# EHR.net
KiCad netlist of a schematic drawn in Altium Designer
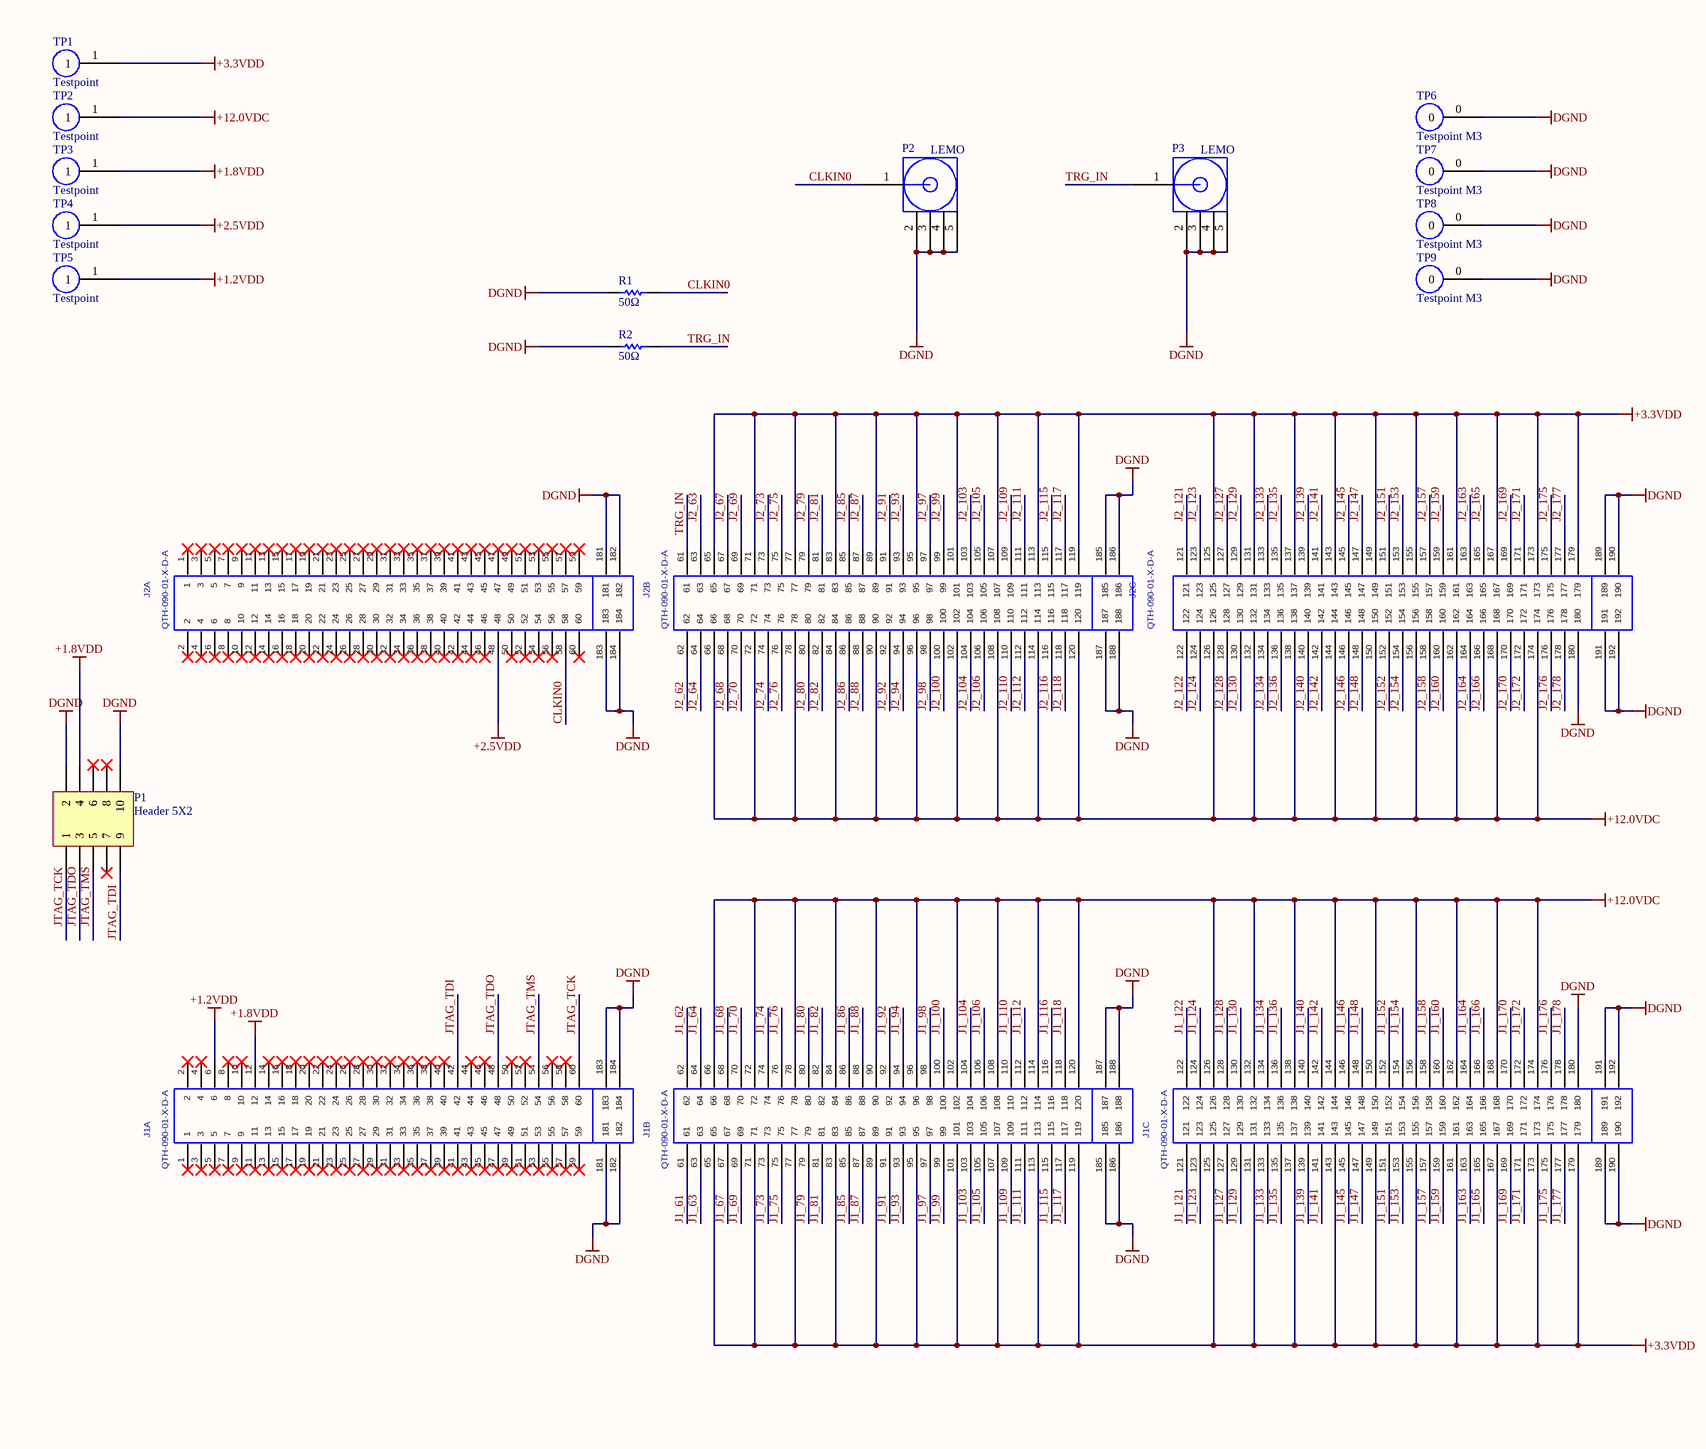
[diagram p0: EHR.SchDoc, left]
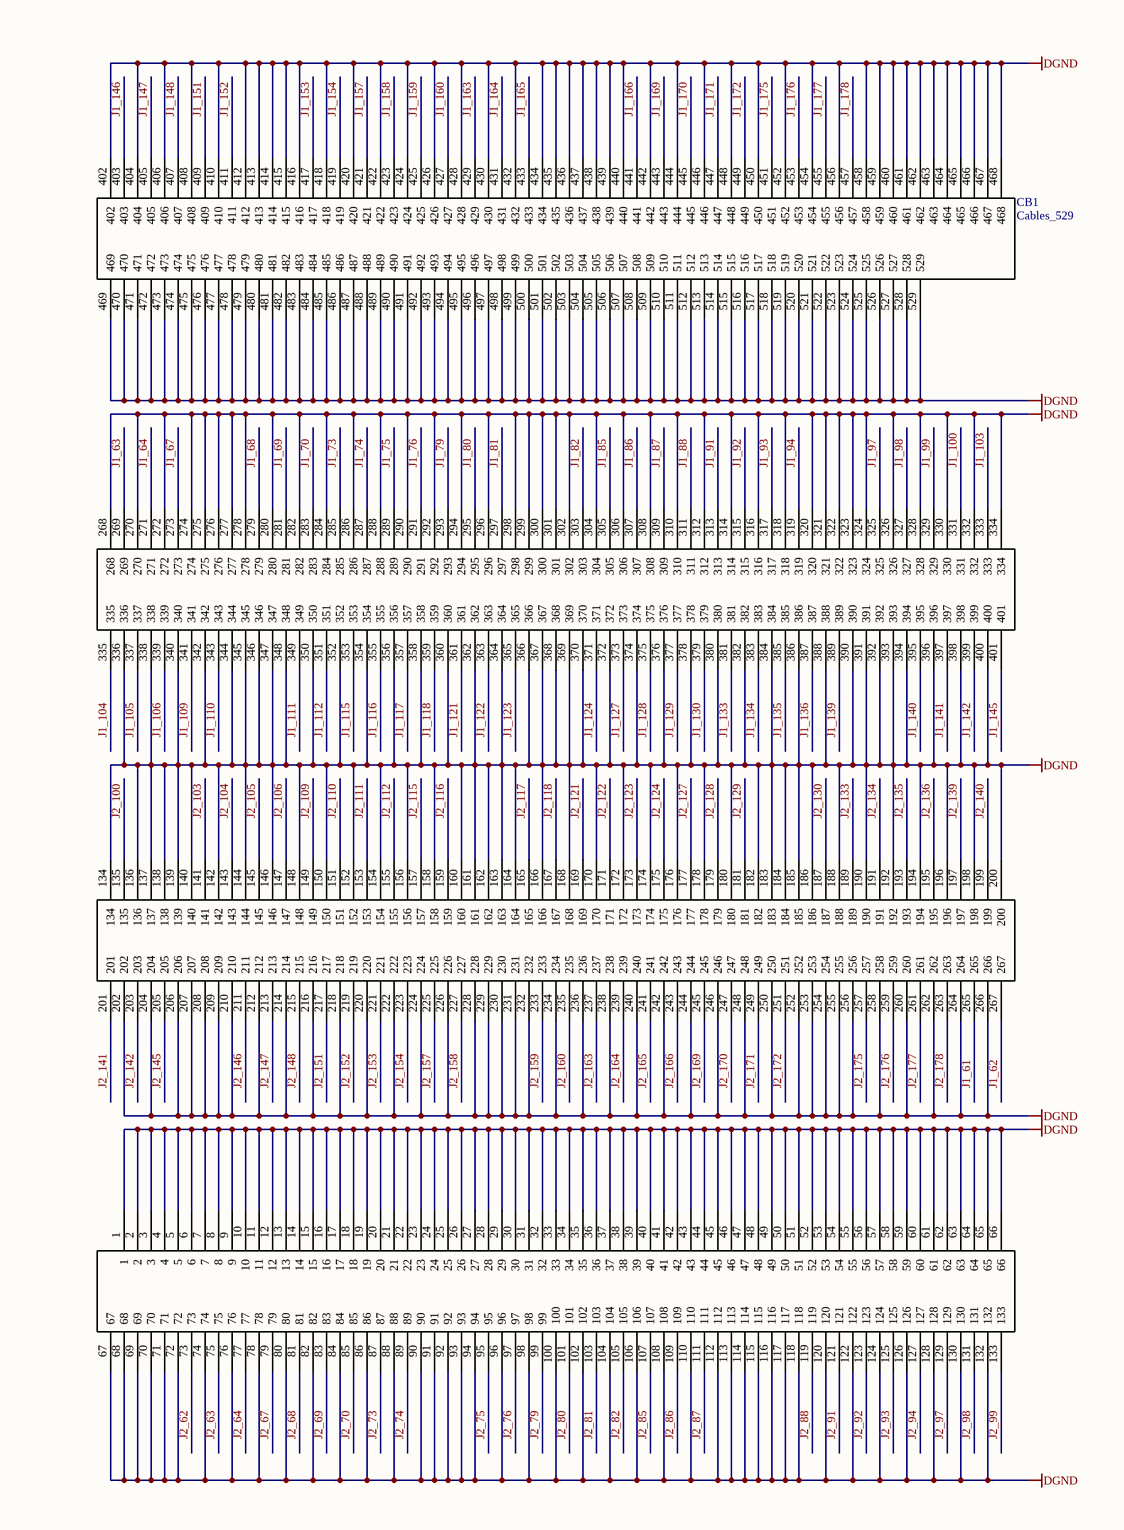
[diagram p1: EHR.SchDoc, right]

(export (version "E")
  (design (tool "Eeschema 10.0.6"))
  (components
    (comp (ref "CB1")
      (value "Cables_529")
      (footprint "EHR23x23_M3")
      (libsource (lib "User_parts") (part "Cables_529"))
    )
    (comp (ref "J1")
      (value "QTH-090-01-X-D-A")
      (footprint "QTH-090-01-X-D-A")
      (description "HIGH SPEED TERMINAL STRIP, .5mm PITCH, 180 PINS.")
      (fields (field (name "MANUFACTURER") "SAMTEC") (field (name "CREATED") "July 30, 2014 - WENDY XIN"))
      (libsource (lib "QTH-090-01-X-D-A") (part "QTH-090-01-X-D-A"))
    )
    (comp (ref "J2")
      (value "QTH-090-01-X-D-A")
      (footprint "QTH-090-01-X-D-A")
      (description "HIGH SPEED TERMINAL STRIP, .5mm PITCH, 180 PINS.")
      (fields (field (name "MANUFACTURER") "SAMTEC") (field (name "CREATED") "July 30, 2014 - WENDY XIN"))
      (libsource (lib "QTH-090-01-X-D-A") (part "QTH-090-01-X-D-A"))
    )
    (comp (ref "P1")
      (value "Header 5X2")
      (footprint "HDR2X5")
      (description "Header, 5-Pin, Dual row")
      (fields (field (name "PUBLISHER") "Altium Limited"))
      (libsource (lib "Miscellaneous Connectors") (part "Header 5X2"))
    )
    (comp (ref "P2") (value "LEMO") (footprint "LEMO_F") (libsource (lib "User_parts") (part "LEMO")))
    (comp (ref "P3") (value "LEMO") (footprint "LEMO_F") (libsource (lib "User_parts") (part "LEMO")))
    (comp (ref "R1")
      (value "50Ω")
      (footprint "AXIAL-0.3")
      (description "Resistor")
      (fields (field (name "PUBLISHER") "Altium Limited"))
      (libsource (lib "Miscellaneous Devices") (part "Res1"))
    )
    (comp (ref "R2")
      (value "50Ω")
      (footprint "AXIAL-0.3")
      (description "Resistor")
      (fields (field (name "PUBLISHER") "Altium Limited"))
      (libsource (lib "Miscellaneous Devices") (part "Res1"))
    )
    (comp (ref "TP1")
      (value "Testpoint")
      (footprint "Pad_mid")
      (description "Testpoint middle")
      (libsource (lib "User_parts") (part "Pad_med"))
    )
    (comp (ref "TP2")
      (value "Testpoint")
      (footprint "Pad_mid")
      (description "Testpoint middle")
      (libsource (lib "User_parts") (part "Pad_med"))
    )
    (comp (ref "TP3")
      (value "Testpoint")
      (footprint "Pad_mid")
      (description "Testpoint middle")
      (libsource (lib "User_parts") (part "Pad_med"))
    )
    (comp (ref "TP4")
      (value "Testpoint")
      (footprint "Pad_mid")
      (description "Testpoint middle")
      (libsource (lib "User_parts") (part "Pad_med"))
    )
    (comp (ref "TP5")
      (value "Testpoint")
      (footprint "Pad_mid")
      (description "Testpoint middle")
      (libsource (lib "User_parts") (part "Pad_med"))
    )
    (comp (ref "TP6")
      (value "Testpoint M3")
      (footprint "Testpoint_M3")
      (libsource (lib "User_parts") (part "Pad_M3"))
    )
    (comp (ref "TP7")
      (value "Testpoint M3")
      (footprint "Testpoint_M3")
      (libsource (lib "User_parts") (part "Pad_M3"))
    )
    (comp (ref "TP8")
      (value "Testpoint M3")
      (footprint "Testpoint_M3")
      (libsource (lib "User_parts") (part "Pad_M3"))
    )
    (comp (ref "TP9")
      (value "Testpoint M3")
      (footprint "Testpoint_M3")
      (libsource (lib "User_parts") (part "Pad_M3"))
    )
  )
  (nets
    (net (code "1") (name "+1.2VDD") (class "Default")
      (node (ref "J1") (pin "6") (pinfunction "6_6") (pintype "passive"))
      (node (ref "TP5") (pin "1") (pinfunction "1_1") (pintype "passive"))
    )
    (net (code "2") (name "+1.8VDD") (class "Default")
      (node (ref "J1") (pin "12") (pinfunction "12_12") (pintype "passive"))
      (node (ref "P1") (pin "4") (pinfunction "4_4") (pintype "passive"))
      (node (ref "TP3") (pin "1") (pinfunction "1_1") (pintype "passive"))
    )
    (net (code "3") (name "+2.5VDD") (class "Default")
      (node (ref "J2") (pin "48") (pinfunction "48_48") (pintype "passive"))
      (node (ref "TP4") (pin "1") (pinfunction "1_1") (pintype "passive"))
    )
    (net (code "4") (name "+3.3VDD") (class "Default")
      (node (ref "J1") (pin "101") (pinfunction "101_101") (pintype "passive"))
      (node (ref "J1") (pin "107") (pinfunction "107_107") (pintype "passive"))
      (node (ref "J1") (pin "113") (pinfunction "113_113") (pintype "passive"))
      (node (ref "J1") (pin "119") (pinfunction "119_119") (pintype "passive"))
      (node (ref "J1") (pin "125") (pinfunction "125_125") (pintype "passive"))
      (node (ref "J1") (pin "131") (pinfunction "131_131") (pintype "passive"))
      (node (ref "J1") (pin "137") (pinfunction "137_137") (pintype "passive"))
      (node (ref "J1") (pin "143") (pinfunction "143_143") (pintype "passive"))
      (node (ref "J1") (pin "149") (pinfunction "149_149") (pintype "passive"))
      (node (ref "J1") (pin "155") (pinfunction "155_155") (pintype "passive"))
      (node (ref "J1") (pin "161") (pinfunction "161_161") (pintype "passive"))
      (node (ref "J1") (pin "167") (pinfunction "167_167") (pintype "passive"))
      (node (ref "J1") (pin "173") (pinfunction "173_173") (pintype "passive"))
      (node (ref "J1") (pin "179") (pinfunction "179_179") (pintype "passive"))
      (node (ref "J1") (pin "65") (pinfunction "65_65") (pintype "passive"))
      (node (ref "J1") (pin "71") (pinfunction "71_71") (pintype "passive"))
      (node (ref "J1") (pin "77") (pinfunction "77_77") (pintype "passive"))
      (node (ref "J1") (pin "83") (pinfunction "83_83") (pintype "passive"))
      (node (ref "J1") (pin "89") (pinfunction "89_89") (pintype "passive"))
      (node (ref "J1") (pin "95") (pinfunction "95_95") (pintype "passive"))
      (node (ref "J2") (pin "101") (pinfunction "101_101") (pintype "passive"))
      (node (ref "J2") (pin "107") (pinfunction "107_107") (pintype "passive"))
      (node (ref "J2") (pin "113") (pinfunction "113_113") (pintype "passive"))
      (node (ref "J2") (pin "119") (pinfunction "119_119") (pintype "passive"))
      (node (ref "J2") (pin "125") (pinfunction "125_125") (pintype "passive"))
      (node (ref "J2") (pin "131") (pinfunction "131_131") (pintype "passive"))
      (node (ref "J2") (pin "137") (pinfunction "137_137") (pintype "passive"))
      (node (ref "J2") (pin "143") (pinfunction "143_143") (pintype "passive"))
      (node (ref "J2") (pin "149") (pinfunction "149_149") (pintype "passive"))
      (node (ref "J2") (pin "155") (pinfunction "155_155") (pintype "passive"))
      (node (ref "J2") (pin "161") (pinfunction "161_161") (pintype "passive"))
      (node (ref "J2") (pin "167") (pinfunction "167_167") (pintype "passive"))
      (node (ref "J2") (pin "173") (pinfunction "173_173") (pintype "passive"))
      (node (ref "J2") (pin "179") (pinfunction "179_179") (pintype "passive"))
      (node (ref "J2") (pin "65") (pinfunction "65_65") (pintype "passive"))
      (node (ref "J2") (pin "71") (pinfunction "71_71") (pintype "passive"))
      (node (ref "J2") (pin "77") (pinfunction "77_77") (pintype "passive"))
      (node (ref "J2") (pin "83") (pinfunction "83_83") (pintype "passive"))
      (node (ref "J2") (pin "89") (pinfunction "89_89") (pintype "passive"))
      (node (ref "J2") (pin "95") (pinfunction "95_95") (pintype "passive"))
      (node (ref "TP1") (pin "1") (pinfunction "1_1") (pintype "passive"))
    )
    (net (code "5") (name "+12.0VDC") (class "Default")
      (node (ref "J1") (pin "102") (pinfunction "102_102") (pintype "passive"))
      (node (ref "J1") (pin "108") (pinfunction "108_108") (pintype "passive"))
      (node (ref "J1") (pin "114") (pinfunction "114_114") (pintype "passive"))
      (node (ref "J1") (pin "120") (pinfunction "120_120") (pintype "passive"))
      (node (ref "J1") (pin "126") (pinfunction "126_126") (pintype "passive"))
      (node (ref "J1") (pin "132") (pinfunction "132_132") (pintype "passive"))
      (node (ref "J1") (pin "138") (pinfunction "138_138") (pintype "passive"))
      (node (ref "J1") (pin "144") (pinfunction "144_144") (pintype "passive"))
      (node (ref "J1") (pin "150") (pinfunction "150_150") (pintype "passive"))
      (node (ref "J1") (pin "156") (pinfunction "156_156") (pintype "passive"))
      (node (ref "J1") (pin "162") (pinfunction "162_162") (pintype "passive"))
      (node (ref "J1") (pin "168") (pinfunction "168_168") (pintype "passive"))
      (node (ref "J1") (pin "174") (pinfunction "174_174") (pintype "passive"))
      (node (ref "J1") (pin "66") (pinfunction "66_66") (pintype "passive"))
      (node (ref "J1") (pin "72") (pinfunction "72_72") (pintype "passive"))
      (node (ref "J1") (pin "78") (pinfunction "78_78") (pintype "passive"))
      (node (ref "J1") (pin "84") (pinfunction "84_84") (pintype "passive"))
      (node (ref "J1") (pin "90") (pinfunction "90_90") (pintype "passive"))
      (node (ref "J1") (pin "96") (pinfunction "96_96") (pintype "passive"))
      (node (ref "J2") (pin "102") (pinfunction "102_102") (pintype "passive"))
      (node (ref "J2") (pin "108") (pinfunction "108_108") (pintype "passive"))
      (node (ref "J2") (pin "114") (pinfunction "114_114") (pintype "passive"))
      (node (ref "J2") (pin "120") (pinfunction "120_120") (pintype "passive"))
      (node (ref "J2") (pin "126") (pinfunction "126_126") (pintype "passive"))
      (node (ref "J2") (pin "132") (pinfunction "132_132") (pintype "passive"))
      (node (ref "J2") (pin "138") (pinfunction "138_138") (pintype "passive"))
      (node (ref "J2") (pin "144") (pinfunction "144_144") (pintype "passive"))
      (node (ref "J2") (pin "150") (pinfunction "150_150") (pintype "passive"))
      (node (ref "J2") (pin "156") (pinfunction "156_156") (pintype "passive"))
      (node (ref "J2") (pin "162") (pinfunction "162_162") (pintype "passive"))
      (node (ref "J2") (pin "168") (pinfunction "168_168") (pintype "passive"))
      (node (ref "J2") (pin "174") (pinfunction "174_174") (pintype "passive"))
      (node (ref "J2") (pin "66") (pinfunction "66_66") (pintype "passive"))
      (node (ref "J2") (pin "72") (pinfunction "72_72") (pintype "passive"))
      (node (ref "J2") (pin "78") (pinfunction "78_78") (pintype "passive"))
      (node (ref "J2") (pin "84") (pinfunction "84_84") (pintype "passive"))
      (node (ref "J2") (pin "90") (pinfunction "90_90") (pintype "passive"))
      (node (ref "J2") (pin "96") (pinfunction "96_96") (pintype "passive"))
      (node (ref "TP2") (pin "1") (pinfunction "1_1") (pintype "passive"))
    )
    (net (code "6") (name "/CLKIN0") (class "Default")
      (node (ref "J2") (pin "58") (pinfunction "58_58") (pintype "passive"))
      (node (ref "P2") (pin "1") (pinfunction "0_1") (pintype "passive"))
      (node (ref "R1") (pin "2") (pinfunction "2_2") (pintype "passive"))
    )
    (net (code "7") (name "/J1_61") (class "Default")
      (node (ref "CB1") (pin "265") (pinfunction "265_265") (pintype "passive"))
      (node (ref "J1") (pin "61") (pinfunction "61_61") (pintype "passive"))
    )
    (net (code "8") (name "/J1_62") (class "Default")
      (node (ref "CB1") (pin "267") (pinfunction "267_267") (pintype "passive"))
      (node (ref "J1") (pin "62") (pinfunction "62_62") (pintype "passive"))
    )
    (net (code "9") (name "/J1_63") (class "Default")
      (node (ref "CB1") (pin "269") (pinfunction "269_269") (pintype "passive"))
      (node (ref "J1") (pin "63") (pinfunction "63_63") (pintype "passive"))
    )
    (net (code "10") (name "/J1_64") (class "Default")
      (node (ref "CB1") (pin "271") (pinfunction "271_271") (pintype "passive"))
      (node (ref "J1") (pin "64") (pinfunction "64_64") (pintype "passive"))
    )
    (net (code "11") (name "/J1_67") (class "Default")
      (node (ref "CB1") (pin "273") (pinfunction "273_273") (pintype "passive"))
      (node (ref "J1") (pin "67") (pinfunction "67_67") (pintype "passive"))
    )
    (net (code "12") (name "/J1_68") (class "Default")
      (node (ref "CB1") (pin "279") (pinfunction "279_279") (pintype "passive"))
      (node (ref "J1") (pin "68") (pinfunction "68_68") (pintype "passive"))
    )
    (net (code "13") (name "/J1_69") (class "Default")
      (node (ref "CB1") (pin "281") (pinfunction "281_281") (pintype "passive"))
      (node (ref "J1") (pin "69") (pinfunction "69_69") (pintype "passive"))
    )
    (net (code "14") (name "/J1_70") (class "Default")
      (node (ref "CB1") (pin "283") (pinfunction "283_283") (pintype "passive"))
      (node (ref "J1") (pin "70") (pinfunction "70_70") (pintype "passive"))
    )
    (net (code "15") (name "/J1_73") (class "Default")
      (node (ref "CB1") (pin "285") (pinfunction "285_285") (pintype "passive"))
      (node (ref "J1") (pin "73") (pinfunction "73_73") (pintype "passive"))
    )
    (net (code "16") (name "/J1_74") (class "Default")
      (node (ref "CB1") (pin "287") (pinfunction "287_287") (pintype "passive"))
      (node (ref "J1") (pin "74") (pinfunction "74_74") (pintype "passive"))
    )
    (net (code "17") (name "/J1_75") (class "Default")
      (node (ref "CB1") (pin "289") (pinfunction "289_289") (pintype "passive"))
      (node (ref "J1") (pin "75") (pinfunction "75_75") (pintype "passive"))
    )
    (net (code "18") (name "/J1_76") (class "Default")
      (node (ref "CB1") (pin "291") (pinfunction "291_291") (pintype "passive"))
      (node (ref "J1") (pin "76") (pinfunction "76_76") (pintype "passive"))
    )
    (net (code "19") (name "/J1_79") (class "Default")
      (node (ref "CB1") (pin "293") (pinfunction "293_293") (pintype "passive"))
      (node (ref "J1") (pin "79") (pinfunction "79_79") (pintype "passive"))
    )
    (net (code "20") (name "/J1_80") (class "Default")
      (node (ref "CB1") (pin "295") (pinfunction "295_295") (pintype "passive"))
      (node (ref "J1") (pin "80") (pinfunction "80_80") (pintype "passive"))
    )
    (net (code "21") (name "/J1_81") (class "Default")
      (node (ref "CB1") (pin "297") (pinfunction "297_297") (pintype "passive"))
      (node (ref "J1") (pin "81") (pinfunction "81_81") (pintype "passive"))
    )
    (net (code "22") (name "/J1_82") (class "Default")
      (node (ref "CB1") (pin "303") (pinfunction "303_303") (pintype "passive"))
      (node (ref "J1") (pin "82") (pinfunction "82_82") (pintype "passive"))
    )
    (net (code "23") (name "/J1_85") (class "Default")
      (node (ref "CB1") (pin "305") (pinfunction "305_305") (pintype "passive"))
      (node (ref "J1") (pin "85") (pinfunction "85_85") (pintype "passive"))
    )
    (net (code "24") (name "/J1_86") (class "Default")
      (node (ref "CB1") (pin "307") (pinfunction "307_307") (pintype "passive"))
      (node (ref "J1") (pin "86") (pinfunction "86_86") (pintype "passive"))
    )
    (net (code "25") (name "/J1_87") (class "Default")
      (node (ref "CB1") (pin "309") (pinfunction "309_309") (pintype "passive"))
      (node (ref "J1") (pin "87") (pinfunction "87_87") (pintype "passive"))
    )
    (net (code "26") (name "/J1_88") (class "Default")
      (node (ref "CB1") (pin "311") (pinfunction "311_311") (pintype "passive"))
      (node (ref "J1") (pin "88") (pinfunction "88_88") (pintype "passive"))
    )
    (net (code "27") (name "/J1_91") (class "Default")
      (node (ref "CB1") (pin "313") (pinfunction "313_313") (pintype "passive"))
      (node (ref "J1") (pin "91") (pinfunction "91_91") (pintype "passive"))
    )
    (net (code "28") (name "/J1_92") (class "Default")
      (node (ref "CB1") (pin "315") (pinfunction "315_315") (pintype "passive"))
      (node (ref "J1") (pin "92") (pinfunction "92_92") (pintype "passive"))
    )
    (net (code "29") (name "/J1_93") (class "Default")
      (node (ref "CB1") (pin "317") (pinfunction "317_317") (pintype "passive"))
      (node (ref "J1") (pin "93") (pinfunction "93_93") (pintype "passive"))
    )
    (net (code "30") (name "/J1_94") (class "Default")
      (node (ref "CB1") (pin "319") (pinfunction "319_319") (pintype "passive"))
      (node (ref "J1") (pin "94") (pinfunction "94_94") (pintype "passive"))
    )
    (net (code "31") (name "/J1_97") (class "Default")
      (node (ref "CB1") (pin "325") (pinfunction "325_325") (pintype "passive"))
      (node (ref "J1") (pin "97") (pinfunction "97_97") (pintype "passive"))
    )
    (net (code "32") (name "/J1_98") (class "Default")
      (node (ref "CB1") (pin "327") (pinfunction "327_327") (pintype "passive"))
      (node (ref "J1") (pin "98") (pinfunction "98_98") (pintype "passive"))
    )
    (net (code "33") (name "/J1_99") (class "Default")
      (node (ref "CB1") (pin "329") (pinfunction "329_329") (pintype "passive"))
      (node (ref "J1") (pin "99") (pinfunction "99_99") (pintype "passive"))
    )
    (net (code "34") (name "/J1_100") (class "Default")
      (node (ref "CB1") (pin "331") (pinfunction "331_331") (pintype "passive"))
      (node (ref "J1") (pin "100") (pinfunction "100_100") (pintype "passive"))
    )
    (net (code "35") (name "/J1_103") (class "Default")
      (node (ref "CB1") (pin "333") (pinfunction "333_333") (pintype "passive"))
      (node (ref "J1") (pin "103") (pinfunction "103_103") (pintype "passive"))
    )
    (net (code "36") (name "/J1_104") (class "Default")
      (node (ref "CB1") (pin "335") (pinfunction "335_335") (pintype "passive"))
      (node (ref "J1") (pin "104") (pinfunction "104_104") (pintype "passive"))
    )
    (net (code "37") (name "/J1_105") (class "Default")
      (node (ref "CB1") (pin "337") (pinfunction "337_337") (pintype "passive"))
      (node (ref "J1") (pin "105") (pinfunction "105_105") (pintype "passive"))
    )
    (net (code "38") (name "/J1_106") (class "Default")
      (node (ref "CB1") (pin "339") (pinfunction "339_339") (pintype "passive"))
      (node (ref "J1") (pin "106") (pinfunction "106_106") (pintype "passive"))
    )
    (net (code "39") (name "/J1_109") (class "Default")
      (node (ref "CB1") (pin "341") (pinfunction "341_341") (pintype "passive"))
      (node (ref "J1") (pin "109") (pinfunction "109_109") (pintype "passive"))
    )
    (net (code "40") (name "/J1_110") (class "Default")
      (node (ref "CB1") (pin "343") (pinfunction "343_343") (pintype "passive"))
      (node (ref "J1") (pin "110") (pinfunction "110_110") (pintype "passive"))
    )
    (net (code "41") (name "/J1_111") (class "Default")
      (node (ref "CB1") (pin "349") (pinfunction "349_349") (pintype "passive"))
      (node (ref "J1") (pin "111") (pinfunction "111_111") (pintype "passive"))
    )
    (net (code "42") (name "/J1_112") (class "Default")
      (node (ref "CB1") (pin "351") (pinfunction "351_351") (pintype "passive"))
      (node (ref "J1") (pin "112") (pinfunction "112_112") (pintype "passive"))
    )
    (net (code "43") (name "/J1_115") (class "Default")
      (node (ref "CB1") (pin "353") (pinfunction "353_353") (pintype "passive"))
      (node (ref "J1") (pin "115") (pinfunction "115_115") (pintype "passive"))
    )
    (net (code "44") (name "/J1_116") (class "Default")
      (node (ref "CB1") (pin "355") (pinfunction "355_355") (pintype "passive"))
      (node (ref "J1") (pin "116") (pinfunction "116_116") (pintype "passive"))
    )
    (net (code "45") (name "/J1_117") (class "Default")
      (node (ref "CB1") (pin "357") (pinfunction "357_357") (pintype "passive"))
      (node (ref "J1") (pin "117") (pinfunction "117_117") (pintype "passive"))
    )
    (net (code "46") (name "/J1_118") (class "Default")
      (node (ref "CB1") (pin "359") (pinfunction "359_359") (pintype "passive"))
      (node (ref "J1") (pin "118") (pinfunction "118_118") (pintype "passive"))
    )
    (net (code "47") (name "/J1_121") (class "Default")
      (node (ref "CB1") (pin "361") (pinfunction "361_361") (pintype "passive"))
      (node (ref "J1") (pin "121") (pinfunction "121_121") (pintype "passive"))
    )
    (net (code "48") (name "/J1_122") (class "Default")
      (node (ref "CB1") (pin "363") (pinfunction "363_363") (pintype "passive"))
      (node (ref "J1") (pin "122") (pinfunction "122_122") (pintype "passive"))
    )
    (net (code "49") (name "/J1_123") (class "Default")
      (node (ref "CB1") (pin "365") (pinfunction "365_365") (pintype "passive"))
      (node (ref "J1") (pin "123") (pinfunction "123_123") (pintype "passive"))
    )
    (net (code "50") (name "/J1_124") (class "Default")
      (node (ref "CB1") (pin "371") (pinfunction "371_371") (pintype "passive"))
      (node (ref "J1") (pin "124") (pinfunction "124_124") (pintype "passive"))
    )
    (net (code "51") (name "/J1_127") (class "Default")
      (node (ref "CB1") (pin "373") (pinfunction "373_373") (pintype "passive"))
      (node (ref "J1") (pin "127") (pinfunction "127_127") (pintype "passive"))
    )
    (net (code "52") (name "/J1_128") (class "Default")
      (node (ref "CB1") (pin "375") (pinfunction "375_375") (pintype "passive"))
      (node (ref "J1") (pin "128") (pinfunction "128_128") (pintype "passive"))
    )
    (net (code "53") (name "/J1_129") (class "Default")
      (node (ref "CB1") (pin "377") (pinfunction "377_377") (pintype "passive"))
      (node (ref "J1") (pin "129") (pinfunction "129_129") (pintype "passive"))
    )
    (net (code "54") (name "/J1_130") (class "Default")
      (node (ref "CB1") (pin "379") (pinfunction "379_379") (pintype "passive"))
      (node (ref "J1") (pin "130") (pinfunction "130_130") (pintype "passive"))
    )
    (net (code "55") (name "/J1_133") (class "Default")
      (node (ref "CB1") (pin "381") (pinfunction "381_381") (pintype "passive"))
      (node (ref "J1") (pin "133") (pinfunction "133_133") (pintype "passive"))
    )
    (net (code "56") (name "/J1_134") (class "Default")
      (node (ref "CB1") (pin "383") (pinfunction "383_383") (pintype "passive"))
      (node (ref "J1") (pin "134") (pinfunction "134_134") (pintype "passive"))
    )
    (net (code "57") (name "/J1_135") (class "Default")
      (node (ref "CB1") (pin "385") (pinfunction "385_385") (pintype "passive"))
      (node (ref "J1") (pin "135") (pinfunction "135_135") (pintype "passive"))
    )
    (net (code "58") (name "/J1_136") (class "Default")
      (node (ref "CB1") (pin "387") (pinfunction "387_387") (pintype "passive"))
      (node (ref "J1") (pin "136") (pinfunction "136_136") (pintype "passive"))
    )
    (net (code "59") (name "/J1_139") (class "Default")
      (node (ref "CB1") (pin "389") (pinfunction "389_389") (pintype "passive"))
      (node (ref "J1") (pin "139") (pinfunction "139_139") (pintype "passive"))
    )
    (net (code "60") (name "/J1_140") (class "Default")
      (node (ref "CB1") (pin "395") (pinfunction "395_395") (pintype "passive"))
      (node (ref "J1") (pin "140") (pinfunction "140_140") (pintype "passive"))
    )
    (net (code "61") (name "/J1_141") (class "Default")
      (node (ref "CB1") (pin "397") (pinfunction "397_397") (pintype "passive"))
      (node (ref "J1") (pin "141") (pinfunction "141_141") (pintype "passive"))
    )
    (net (code "62") (name "/J1_142") (class "Default")
      (node (ref "CB1") (pin "399") (pinfunction "399_399") (pintype "passive"))
      (node (ref "J1") (pin "142") (pinfunction "142_142") (pintype "passive"))
    )
    (net (code "63") (name "/J1_145") (class "Default")
      (node (ref "CB1") (pin "401") (pinfunction "401_401") (pintype "passive"))
      (node (ref "J1") (pin "145") (pinfunction "145_145") (pintype "passive"))
    )
    (net (code "64") (name "/J1_146") (class "Default")
      (node (ref "CB1") (pin "403") (pinfunction "403_403") (pintype "passive"))
      (node (ref "J1") (pin "146") (pinfunction "146_146") (pintype "passive"))
    )
    (net (code "65") (name "/J1_147") (class "Default")
      (node (ref "CB1") (pin "405") (pinfunction "405_405") (pintype "passive"))
      (node (ref "J1") (pin "147") (pinfunction "147_147") (pintype "passive"))
    )
    (net (code "66") (name "/J1_148") (class "Default")
      (node (ref "CB1") (pin "407") (pinfunction "407_407") (pintype "passive"))
      (node (ref "J1") (pin "148") (pinfunction "148_148") (pintype "passive"))
    )
    (net (code "67") (name "/J1_151") (class "Default")
      (node (ref "CB1") (pin "409") (pinfunction "409_409") (pintype "passive"))
      (node (ref "J1") (pin "151") (pinfunction "151_151") (pintype "passive"))
    )
    (net (code "68") (name "/J1_152") (class "Default")
      (node (ref "CB1") (pin "411") (pinfunction "411_411") (pintype "passive"))
      (node (ref "J1") (pin "152") (pinfunction "152_152") (pintype "passive"))
    )
    (net (code "69") (name "/J1_153") (class "Default")
      (node (ref "CB1") (pin "417") (pinfunction "417_417") (pintype "passive"))
      (node (ref "J1") (pin "153") (pinfunction "153_153") (pintype "passive"))
    )
    (net (code "70") (name "/J1_154") (class "Default")
      (node (ref "CB1") (pin "419") (pinfunction "419_419") (pintype "passive"))
      (node (ref "J1") (pin "154") (pinfunction "154_154") (pintype "passive"))
    )
    (net (code "71") (name "/J1_157") (class "Default")
      (node (ref "CB1") (pin "421") (pinfunction "421_421") (pintype "passive"))
      (node (ref "J1") (pin "157") (pinfunction "157_157") (pintype "passive"))
    )
    (net (code "72") (name "/J1_158") (class "Default")
      (node (ref "CB1") (pin "423") (pinfunction "423_423") (pintype "passive"))
      (node (ref "J1") (pin "158") (pinfunction "158_158") (pintype "passive"))
    )
    (net (code "73") (name "/J1_159") (class "Default")
      (node (ref "CB1") (pin "425") (pinfunction "425_425") (pintype "passive"))
      (node (ref "J1") (pin "159") (pinfunction "159_159") (pintype "passive"))
    )
    (net (code "74") (name "/J1_160") (class "Default")
      (node (ref "CB1") (pin "427") (pinfunction "427_427") (pintype "passive"))
      (node (ref "J1") (pin "160") (pinfunction "160_160") (pintype "passive"))
    )
    (net (code "75") (name "/J1_163") (class "Default")
      (node (ref "CB1") (pin "429") (pinfunction "429_429") (pintype "passive"))
      (node (ref "J1") (pin "163") (pinfunction "163_163") (pintype "passive"))
    )
    (net (code "76") (name "/J1_164") (class "Default")
      (node (ref "CB1") (pin "431") (pinfunction "431_431") (pintype "passive"))
      (node (ref "J1") (pin "164") (pinfunction "164_164") (pintype "passive"))
    )
    (net (code "77") (name "/J1_165") (class "Default")
      (node (ref "CB1") (pin "433") (pinfunction "433_433") (pintype "passive"))
      (node (ref "J1") (pin "165") (pinfunction "165_165") (pintype "passive"))
    )
    (net (code "78") (name "/J1_166") (class "Default")
      (node (ref "CB1") (pin "441") (pinfunction "441_441") (pintype "passive"))
      (node (ref "J1") (pin "166") (pinfunction "166_166") (pintype "passive"))
    )
    (net (code "79") (name "/J1_169") (class "Default")
      (node (ref "CB1") (pin "443") (pinfunction "443_443") (pintype "passive"))
      (node (ref "J1") (pin "169") (pinfunction "169_169") (pintype "passive"))
    )
    (net (code "80") (name "/J1_170") (class "Default")
      (node (ref "CB1") (pin "445") (pinfunction "445_445") (pintype "passive"))
      (node (ref "J1") (pin "170") (pinfunction "170_170") (pintype "passive"))
    )
    (net (code "81") (name "/J1_171") (class "Default")
      (node (ref "CB1") (pin "447") (pinfunction "447_447") (pintype "passive"))
      (node (ref "J1") (pin "171") (pinfunction "171_171") (pintype "passive"))
    )
    (net (code "82") (name "/J1_172") (class "Default")
      (node (ref "CB1") (pin "449") (pinfunction "449_449") (pintype "passive"))
      (node (ref "J1") (pin "172") (pinfunction "172_172") (pintype "passive"))
    )
    (net (code "83") (name "/J1_175") (class "Default")
      (node (ref "CB1") (pin "451") (pinfunction "451_451") (pintype "passive"))
      (node (ref "J1") (pin "175") (pinfunction "175_175") (pintype "passive"))
    )
    (net (code "84") (name "/J1_176") (class "Default")
      (node (ref "CB1") (pin "453") (pinfunction "453_453") (pintype "passive"))
      (node (ref "J1") (pin "176") (pinfunction "176_176") (pintype "passive"))
    )
    (net (code "85") (name "/J1_177") (class "Default")
      (node (ref "CB1") (pin "455") (pinfunction "455_455") (pintype "passive"))
      (node (ref "J1") (pin "177") (pinfunction "177_177") (pintype "passive"))
    )
    (net (code "86") (name "/J1_178") (class "Default")
      (node (ref "CB1") (pin "457") (pinfunction "457_457") (pintype "passive"))
      (node (ref "J1") (pin "178") (pinfunction "178_178") (pintype "passive"))
    )
    (net (code "87") (name "/J2_62") (class "Default")
      (node (ref "CB1") (pin "73") (pinfunction "73_73") (pintype "passive"))
      (node (ref "J2") (pin "62") (pinfunction "62_62") (pintype "passive"))
    )
    (net (code "88") (name "/J2_63") (class "Default")
      (node (ref "CB1") (pin "75") (pinfunction "75_75") (pintype "passive"))
      (node (ref "J2") (pin "63") (pinfunction "63_63") (pintype "passive"))
    )
    (net (code "89") (name "/J2_64") (class "Default")
      (node (ref "CB1") (pin "77") (pinfunction "77_77") (pintype "passive"))
      (node (ref "J2") (pin "64") (pinfunction "64_64") (pintype "passive"))
    )
    (net (code "90") (name "/J2_67") (class "Default")
      (node (ref "CB1") (pin "79") (pinfunction "79_79") (pintype "passive"))
      (node (ref "J2") (pin "67") (pinfunction "67_67") (pintype "passive"))
    )
    (net (code "91") (name "/J2_68") (class "Default")
      (node (ref "CB1") (pin "81") (pinfunction "81_81") (pintype "passive"))
      (node (ref "J2") (pin "68") (pinfunction "68_68") (pintype "passive"))
    )
    (net (code "92") (name "/J2_69") (class "Default")
      (node (ref "CB1") (pin "83") (pinfunction "83_83") (pintype "passive"))
      (node (ref "J2") (pin "69") (pinfunction "69_69") (pintype "passive"))
    )
    (net (code "93") (name "/J2_70") (class "Default")
      (node (ref "CB1") (pin "85") (pinfunction "85_85") (pintype "passive"))
      (node (ref "J2") (pin "70") (pinfunction "70_70") (pintype "passive"))
    )
    (net (code "94") (name "/J2_73") (class "Default")
      (node (ref "CB1") (pin "87") (pinfunction "87_87") (pintype "passive"))
      (node (ref "J2") (pin "73") (pinfunction "73_73") (pintype "passive"))
    )
    (net (code "95") (name "/J2_74") (class "Default")
      (node (ref "CB1") (pin "89") (pinfunction "89_89") (pintype "passive"))
      (node (ref "J2") (pin "74") (pinfunction "74_74") (pintype "passive"))
    )
    (net (code "96") (name "/J2_75") (class "Default")
      (node (ref "CB1") (pin "95") (pinfunction "95_95") (pintype "passive"))
      (node (ref "J2") (pin "75") (pinfunction "75_75") (pintype "passive"))
    )
    (net (code "97") (name "/J2_76") (class "Default")
      (node (ref "CB1") (pin "97") (pinfunction "97_97") (pintype "passive"))
      (node (ref "J2") (pin "76") (pinfunction "76_76") (pintype "passive"))
    )
    (net (code "98") (name "/J2_79") (class "Default")
      (node (ref "CB1") (pin "99") (pinfunction "99_99") (pintype "passive"))
      (node (ref "J2") (pin "79") (pinfunction "79_79") (pintype "passive"))
    )
    (net (code "99") (name "/J2_80") (class "Default")
      (node (ref "CB1") (pin "101") (pinfunction "101_101") (pintype "passive"))
      (node (ref "J2") (pin "80") (pinfunction "80_80") (pintype "passive"))
    )
    (net (code "100") (name "/J2_81") (class "Default")
      (node (ref "CB1") (pin "103") (pinfunction "103_103") (pintype "passive"))
      (node (ref "J2") (pin "81") (pinfunction "81_81") (pintype "passive"))
    )
    (net (code "101") (name "/J2_82") (class "Default")
      (node (ref "CB1") (pin "105") (pinfunction "105_105") (pintype "passive"))
      (node (ref "J2") (pin "82") (pinfunction "82_82") (pintype "passive"))
    )
    (net (code "102") (name "/J2_85") (class "Default")
      (node (ref "CB1") (pin "107") (pinfunction "107_107") (pintype "passive"))
      (node (ref "J2") (pin "85") (pinfunction "85_85") (pintype "passive"))
    )
    (net (code "103") (name "/J2_86") (class "Default")
      (node (ref "CB1") (pin "109") (pinfunction "109_109") (pintype "passive"))
      (node (ref "J2") (pin "86") (pinfunction "86_86") (pintype "passive"))
    )
    (net (code "104") (name "/J2_87") (class "Default")
      (node (ref "CB1") (pin "111") (pinfunction "111_111") (pintype "passive"))
      (node (ref "J2") (pin "87") (pinfunction "87_87") (pintype "passive"))
    )
    (net (code "105") (name "/J2_88") (class "Default")
      (node (ref "CB1") (pin "119") (pinfunction "119_119") (pintype "passive"))
      (node (ref "J2") (pin "88") (pinfunction "88_88") (pintype "passive"))
    )
    (net (code "106") (name "/J2_91") (class "Default")
      (node (ref "CB1") (pin "121") (pinfunction "121_121") (pintype "passive"))
      (node (ref "J2") (pin "91") (pinfunction "91_91") (pintype "passive"))
    )
    (net (code "107") (name "/J2_92") (class "Default")
      (node (ref "CB1") (pin "123") (pinfunction "123_123") (pintype "passive"))
      (node (ref "J2") (pin "92") (pinfunction "92_92") (pintype "passive"))
    )
    (net (code "108") (name "/J2_93") (class "Default")
      (node (ref "CB1") (pin "125") (pinfunction "125_125") (pintype "passive"))
      (node (ref "J2") (pin "93") (pinfunction "93_93") (pintype "passive"))
    )
    (net (code "109") (name "/J2_94") (class "Default")
      (node (ref "CB1") (pin "127") (pinfunction "127_127") (pintype "passive"))
      (node (ref "J2") (pin "94") (pinfunction "94_94") (pintype "passive"))
    )
    (net (code "110") (name "/J2_97") (class "Default")
      (node (ref "CB1") (pin "129") (pinfunction "129_129") (pintype "passive"))
      (node (ref "J2") (pin "97") (pinfunction "97_97") (pintype "passive"))
    )
    (net (code "111") (name "/J2_98") (class "Default")
      (node (ref "CB1") (pin "131") (pinfunction "131_131") (pintype "passive"))
      (node (ref "J2") (pin "98") (pinfunction "98_98") (pintype "passive"))
    )
    (net (code "112") (name "/J2_99") (class "Default")
      (node (ref "CB1") (pin "133") (pinfunction "133_133") (pintype "passive"))
      (node (ref "J2") (pin "99") (pinfunction "99_99") (pintype "passive"))
    )
    (net (code "113") (name "/J2_100") (class "Default")
      (node (ref "CB1") (pin "135") (pinfunction "135_135") (pintype "passive"))
      (node (ref "J2") (pin "100") (pinfunction "100_100") (pintype "passive"))
    )
    (net (code "114") (name "/J2_103") (class "Default")
      (node (ref "CB1") (pin "141") (pinfunction "141_141") (pintype "passive"))
      (node (ref "J2") (pin "103") (pinfunction "103_103") (pintype "passive"))
    )
    (net (code "115") (name "/J2_104") (class "Default")
      (node (ref "CB1") (pin "143") (pinfunction "143_143") (pintype "passive"))
      (node (ref "J2") (pin "104") (pinfunction "104_104") (pintype "passive"))
    )
    (net (code "116") (name "/J2_105") (class "Default")
      (node (ref "CB1") (pin "145") (pinfunction "145_145") (pintype "passive"))
      (node (ref "J2") (pin "105") (pinfunction "105_105") (pintype "passive"))
    )
    (net (code "117") (name "/J2_106") (class "Default")
      (node (ref "CB1") (pin "147") (pinfunction "147_147") (pintype "passive"))
      (node (ref "J2") (pin "106") (pinfunction "106_106") (pintype "passive"))
    )
    (net (code "118") (name "/J2_109") (class "Default")
      (node (ref "CB1") (pin "149") (pinfunction "149_149") (pintype "passive"))
      (node (ref "J2") (pin "109") (pinfunction "109_109") (pintype "passive"))
    )
    (net (code "119") (name "/J2_110") (class "Default")
      (node (ref "CB1") (pin "151") (pinfunction "151_151") (pintype "passive"))
      (node (ref "J2") (pin "110") (pinfunction "110_110") (pintype "passive"))
    )
    (net (code "120") (name "/J2_111") (class "Default")
      (node (ref "CB1") (pin "153") (pinfunction "153_153") (pintype "passive"))
      (node (ref "J2") (pin "111") (pinfunction "111_111") (pintype "passive"))
    )
    (net (code "121") (name "/J2_112") (class "Default")
      (node (ref "CB1") (pin "155") (pinfunction "155_155") (pintype "passive"))
      (node (ref "J2") (pin "112") (pinfunction "112_112") (pintype "passive"))
    )
    (net (code "122") (name "/J2_115") (class "Default")
      (node (ref "CB1") (pin "157") (pinfunction "157_157") (pintype "passive"))
      (node (ref "J2") (pin "115") (pinfunction "115_115") (pintype "passive"))
    )
    (net (code "123") (name "/J2_116") (class "Default")
      (node (ref "CB1") (pin "159") (pinfunction "159_159") (pintype "passive"))
      (node (ref "J2") (pin "116") (pinfunction "116_116") (pintype "passive"))
    )
    (net (code "124") (name "/J2_117") (class "Default")
      (node (ref "CB1") (pin "165") (pinfunction "165_165") (pintype "passive"))
      (node (ref "J2") (pin "117") (pinfunction "117_117") (pintype "passive"))
    )
    (net (code "125") (name "/J2_118") (class "Default")
      (node (ref "CB1") (pin "167") (pinfunction "167_167") (pintype "passive"))
      (node (ref "J2") (pin "118") (pinfunction "118_118") (pintype "passive"))
    )
    (net (code "126") (name "/J2_121") (class "Default")
      (node (ref "CB1") (pin "169") (pinfunction "169_169") (pintype "passive"))
      (node (ref "J2") (pin "121") (pinfunction "121_121") (pintype "passive"))
    )
    (net (code "127") (name "/J2_122") (class "Default")
      (node (ref "CB1") (pin "171") (pinfunction "171_171") (pintype "passive"))
      (node (ref "J2") (pin "122") (pinfunction "122_122") (pintype "passive"))
    )
    (net (code "128") (name "/J2_123") (class "Default")
      (node (ref "CB1") (pin "173") (pinfunction "173_173") (pintype "passive"))
      (node (ref "J2") (pin "123") (pinfunction "123_123") (pintype "passive"))
    )
    (net (code "129") (name "/J2_124") (class "Default")
      (node (ref "CB1") (pin "175") (pinfunction "175_175") (pintype "passive"))
      (node (ref "J2") (pin "124") (pinfunction "124_124") (pintype "passive"))
    )
    (net (code "130") (name "/J2_127") (class "Default")
      (node (ref "CB1") (pin "177") (pinfunction "177_177") (pintype "passive"))
      (node (ref "J2") (pin "127") (pinfunction "127_127") (pintype "passive"))
    )
    (net (code "131") (name "/J2_128") (class "Default")
      (node (ref "CB1") (pin "179") (pinfunction "179_179") (pintype "passive"))
      (node (ref "J2") (pin "128") (pinfunction "128_128") (pintype "passive"))
    )
    (net (code "132") (name "/J2_129") (class "Default")
      (node (ref "CB1") (pin "181") (pinfunction "181_181") (pintype "passive"))
      (node (ref "J2") (pin "129") (pinfunction "129_129") (pintype "passive"))
    )
    (net (code "133") (name "/J2_130") (class "Default")
      (node (ref "CB1") (pin "187") (pinfunction "187_187") (pintype "passive"))
      (node (ref "J2") (pin "130") (pinfunction "130_130") (pintype "passive"))
    )
    (net (code "134") (name "/J2_133") (class "Default")
      (node (ref "CB1") (pin "189") (pinfunction "189_189") (pintype "passive"))
      (node (ref "J2") (pin "133") (pinfunction "133_133") (pintype "passive"))
    )
    (net (code "135") (name "/J2_134") (class "Default")
      (node (ref "CB1") (pin "191") (pinfunction "191_191") (pintype "passive"))
      (node (ref "J2") (pin "134") (pinfunction "134_134") (pintype "passive"))
    )
    (net (code "136") (name "/J2_135") (class "Default")
      (node (ref "CB1") (pin "193") (pinfunction "193_193") (pintype "passive"))
      (node (ref "J2") (pin "135") (pinfunction "135_135") (pintype "passive"))
    )
    (net (code "137") (name "/J2_136") (class "Default")
      (node (ref "CB1") (pin "195") (pinfunction "195_195") (pintype "passive"))
      (node (ref "J2") (pin "136") (pinfunction "136_136") (pintype "passive"))
    )
    (net (code "138") (name "/J2_139") (class "Default")
      (node (ref "CB1") (pin "197") (pinfunction "197_197") (pintype "passive"))
      (node (ref "J2") (pin "139") (pinfunction "139_139") (pintype "passive"))
    )
    (net (code "139") (name "/J2_140") (class "Default")
      (node (ref "CB1") (pin "199") (pinfunction "199_199") (pintype "passive"))
      (node (ref "J2") (pin "140") (pinfunction "140_140") (pintype "passive"))
    )
    (net (code "140") (name "/J2_141") (class "Default")
      (node (ref "CB1") (pin "201") (pinfunction "201_201") (pintype "passive"))
      (node (ref "J2") (pin "141") (pinfunction "141_141") (pintype "passive"))
    )
    (net (code "141") (name "/J2_142") (class "Default")
      (node (ref "CB1") (pin "203") (pinfunction "203_203") (pintype "passive"))
      (node (ref "J2") (pin "142") (pinfunction "142_142") (pintype "passive"))
    )
    (net (code "142") (name "/J2_145") (class "Default")
      (node (ref "CB1") (pin "205") (pinfunction "205_205") (pintype "passive"))
      (node (ref "J2") (pin "145") (pinfunction "145_145") (pintype "passive"))
    )
    (net (code "143") (name "/J2_146") (class "Default")
      (node (ref "CB1") (pin "211") (pinfunction "211_211") (pintype "passive"))
      (node (ref "J2") (pin "146") (pinfunction "146_146") (pintype "passive"))
    )
    (net (code "144") (name "/J2_147") (class "Default")
      (node (ref "CB1") (pin "213") (pinfunction "213_213") (pintype "passive"))
      (node (ref "J2") (pin "147") (pinfunction "147_147") (pintype "passive"))
    )
    (net (code "145") (name "/J2_148") (class "Default")
      (node (ref "CB1") (pin "215") (pinfunction "215_215") (pintype "passive"))
      (node (ref "J2") (pin "148") (pinfunction "148_148") (pintype "passive"))
    )
    (net (code "146") (name "/J2_151") (class "Default")
      (node (ref "CB1") (pin "217") (pinfunction "217_217") (pintype "passive"))
      (node (ref "J2") (pin "151") (pinfunction "151_151") (pintype "passive"))
    )
    (net (code "147") (name "/J2_152") (class "Default")
      (node (ref "CB1") (pin "219") (pinfunction "219_219") (pintype "passive"))
      (node (ref "J2") (pin "152") (pinfunction "152_152") (pintype "passive"))
    )
    (net (code "148") (name "/J2_153") (class "Default")
      (node (ref "CB1") (pin "221") (pinfunction "221_221") (pintype "passive"))
      (node (ref "J2") (pin "153") (pinfunction "153_153") (pintype "passive"))
    )
    (net (code "149") (name "/J2_154") (class "Default")
      (node (ref "CB1") (pin "223") (pinfunction "223_223") (pintype "passive"))
      (node (ref "J2") (pin "154") (pinfunction "154_154") (pintype "passive"))
    )
    (net (code "150") (name "/J2_157") (class "Default")
      (node (ref "CB1") (pin "225") (pinfunction "225_225") (pintype "passive"))
      (node (ref "J2") (pin "157") (pinfunction "157_157") (pintype "passive"))
    )
    (net (code "151") (name "/J2_158") (class "Default")
      (node (ref "CB1") (pin "227") (pinfunction "227_227") (pintype "passive"))
      (node (ref "J2") (pin "158") (pinfunction "158_158") (pintype "passive"))
    )
    (net (code "152") (name "/J2_159") (class "Default")
      (node (ref "CB1") (pin "233") (pinfunction "233_233") (pintype "passive"))
      (node (ref "J2") (pin "159") (pinfunction "159_159") (pintype "passive"))
    )
    (net (code "153") (name "/J2_160") (class "Default")
      (node (ref "CB1") (pin "235") (pinfunction "235_235") (pintype "passive"))
      (node (ref "J2") (pin "160") (pinfunction "160_160") (pintype "passive"))
    )
    (net (code "154") (name "/J2_163") (class "Default")
      (node (ref "CB1") (pin "237") (pinfunction "237_237") (pintype "passive"))
      (node (ref "J2") (pin "163") (pinfunction "163_163") (pintype "passive"))
    )
    (net (code "155") (name "/J2_164") (class "Default")
      (node (ref "CB1") (pin "239") (pinfunction "239_239") (pintype "passive"))
      (node (ref "J2") (pin "164") (pinfunction "164_164") (pintype "passive"))
    )
    (net (code "156") (name "/J2_165") (class "Default")
      (node (ref "CB1") (pin "241") (pinfunction "241_241") (pintype "passive"))
      (node (ref "J2") (pin "165") (pinfunction "165_165") (pintype "passive"))
    )
    (net (code "157") (name "/J2_166") (class "Default")
      (node (ref "CB1") (pin "243") (pinfunction "243_243") (pintype "passive"))
      (node (ref "J2") (pin "166") (pinfunction "166_166") (pintype "passive"))
    )
    (net (code "158") (name "/J2_169") (class "Default")
      (node (ref "CB1") (pin "245") (pinfunction "245_245") (pintype "passive"))
      (node (ref "J2") (pin "169") (pinfunction "169_169") (pintype "passive"))
    )
    (net (code "159") (name "/J2_170") (class "Default")
      (node (ref "CB1") (pin "247") (pinfunction "247_247") (pintype "passive"))
      (node (ref "J2") (pin "170") (pinfunction "170_170") (pintype "passive"))
    )
    (net (code "160") (name "/J2_171") (class "Default")
      (node (ref "CB1") (pin "249") (pinfunction "249_249") (pintype "passive"))
      (node (ref "J2") (pin "171") (pinfunction "171_171") (pintype "passive"))
    )
    (net (code "161") (name "/J2_172") (class "Default")
      (node (ref "CB1") (pin "251") (pinfunction "251_251") (pintype "passive"))
      (node (ref "J2") (pin "172") (pinfunction "172_172") (pintype "passive"))
    )
    (net (code "162") (name "/J2_175") (class "Default")
      (node (ref "CB1") (pin "257") (pinfunction "257_257") (pintype "passive"))
      (node (ref "J2") (pin "175") (pinfunction "175_175") (pintype "passive"))
    )
    (net (code "163") (name "/J2_176") (class "Default")
      (node (ref "CB1") (pin "259") (pinfunction "259_259") (pintype "passive"))
      (node (ref "J2") (pin "176") (pinfunction "176_176") (pintype "passive"))
    )
    (net (code "164") (name "/J2_177") (class "Default")
      (node (ref "CB1") (pin "261") (pinfunction "261_261") (pintype "passive"))
      (node (ref "J2") (pin "177") (pinfunction "177_177") (pintype "passive"))
    )
    (net (code "165") (name "/J2_178") (class "Default")
      (node (ref "CB1") (pin "263") (pinfunction "263_263") (pintype "passive"))
      (node (ref "J2") (pin "178") (pinfunction "178_178") (pintype "passive"))
    )
    (net (code "166") (name "/JTAG_TCK") (class "Default")
      (node (ref "J1") (pin "60") (pinfunction "60_60") (pintype "passive"))
      (node (ref "P1") (pin "1") (pinfunction "1_1") (pintype "passive"))
    )
    (net (code "167") (name "/JTAG_TDI") (class "Default")
      (node (ref "J1") (pin "42") (pinfunction "42_42") (pintype "passive"))
      (node (ref "P1") (pin "9") (pinfunction "9_9") (pintype "passive"))
    )
    (net (code "168") (name "/JTAG_TDO") (class "Default")
      (node (ref "J1") (pin "48") (pinfunction "48_48") (pintype "passive"))
      (node (ref "P1") (pin "3") (pinfunction "3_3") (pintype "passive"))
    )
    (net (code "169") (name "/JTAG_TMS") (class "Default")
      (node (ref "J1") (pin "54") (pinfunction "54_54") (pintype "passive"))
      (node (ref "P1") (pin "5") (pinfunction "5_5") (pintype "passive"))
    )
    (net (code "170") (name "/TRG_IN") (class "Default")
      (node (ref "J2") (pin "61") (pinfunction "61_61") (pintype "passive"))
      (node (ref "P3") (pin "1") (pinfunction "0_1") (pintype "passive"))
      (node (ref "R2") (pin "2") (pinfunction "2_2") (pintype "passive"))
    )
    (net (code "171") (name "DGND") (class "Default")
      (node (ref "CB1") (pin "1") (pinfunction "1_1") (pintype "passive"))
      (node (ref "CB1") (pin "10") (pinfunction "10_10") (pintype "passive"))
      (node (ref "CB1") (pin "100") (pinfunction "100_100") (pintype "passive"))
      (node (ref "CB1") (pin "102") (pinfunction "102_102") (pintype "passive"))
      (node (ref "CB1") (pin "104") (pinfunction "104_104") (pintype "passive"))
      (node (ref "CB1") (pin "106") (pinfunction "106_106") (pintype "passive"))
      (node (ref "CB1") (pin "108") (pinfunction "108_108") (pintype "passive"))
      (node (ref "CB1") (pin "11") (pinfunction "11_11") (pintype "passive"))
      (node (ref "CB1") (pin "110") (pinfunction "110_110") (pintype "passive"))
      (node (ref "CB1") (pin "112") (pinfunction "112_112") (pintype "passive"))
      (node (ref "CB1") (pin "113") (pinfunction "113_113") (pintype "passive"))
      (node (ref "CB1") (pin "114") (pinfunction "114_114") (pintype "passive"))
      (node (ref "CB1") (pin "115") (pinfunction "115_115") (pintype "passive"))
      (node (ref "CB1") (pin "116") (pinfunction "116_116") (pintype "passive"))
      (node (ref "CB1") (pin "117") (pinfunction "117_117") (pintype "passive"))
      (node (ref "CB1") (pin "118") (pinfunction "118_118") (pintype "passive"))
      (node (ref "CB1") (pin "12") (pinfunction "12_12") (pintype "passive"))
      (node (ref "CB1") (pin "120") (pinfunction "120_120") (pintype "passive"))
      (node (ref "CB1") (pin "122") (pinfunction "122_122") (pintype "passive"))
      (node (ref "CB1") (pin "124") (pinfunction "124_124") (pintype "passive"))
      (node (ref "CB1") (pin "126") (pinfunction "126_126") (pintype "passive"))
      (node (ref "CB1") (pin "128") (pinfunction "128_128") (pintype "passive"))
      (node (ref "CB1") (pin "13") (pinfunction "13_13") (pintype "passive"))
      (node (ref "CB1") (pin "130") (pinfunction "130_130") (pintype "passive"))
      (node (ref "CB1") (pin "132") (pinfunction "132_132") (pintype "passive"))
      (node (ref "CB1") (pin "134") (pinfunction "134_134") (pintype "passive"))
      (node (ref "CB1") (pin "136") (pinfunction "136_136") (pintype "passive"))
      (node (ref "CB1") (pin "137") (pinfunction "137_137") (pintype "passive"))
      (node (ref "CB1") (pin "138") (pinfunction "138_138") (pintype "passive"))
      (node (ref "CB1") (pin "139") (pinfunction "139_139") (pintype "passive"))
      (node (ref "CB1") (pin "14") (pinfunction "14_14") (pintype "passive"))
      (node (ref "CB1") (pin "140") (pinfunction "140_140") (pintype "passive"))
      (node (ref "CB1") (pin "142") (pinfunction "142_142") (pintype "passive"))
      (node (ref "CB1") (pin "144") (pinfunction "144_144") (pintype "passive"))
      (node (ref "CB1") (pin "146") (pinfunction "146_146") (pintype "passive"))
      (node (ref "CB1") (pin "148") (pinfunction "148_148") (pintype "passive"))
      (node (ref "CB1") (pin "15") (pinfunction "15_15") (pintype "passive"))
      (node (ref "CB1") (pin "150") (pinfunction "150_150") (pintype "passive"))
      (node (ref "CB1") (pin "152") (pinfunction "152_152") (pintype "passive"))
      (node (ref "CB1") (pin "154") (pinfunction "154_154") (pintype "passive"))
      (node (ref "CB1") (pin "156") (pinfunction "156_156") (pintype "passive"))
      (node (ref "CB1") (pin "158") (pinfunction "158_158") (pintype "passive"))
      (node (ref "CB1") (pin "16") (pinfunction "16_16") (pintype "passive"))
      (node (ref "CB1") (pin "160") (pinfunction "160_160") (pintype "passive"))
      (node (ref "CB1") (pin "161") (pinfunction "161_161") (pintype "passive"))
      (node (ref "CB1") (pin "162") (pinfunction "162_162") (pintype "passive"))
      (node (ref "CB1") (pin "163") (pinfunction "163_163") (pintype "passive"))
      (node (ref "CB1") (pin "164") (pinfunction "164_164") (pintype "passive"))
      (node (ref "CB1") (pin "166") (pinfunction "166_166") (pintype "passive"))
      (node (ref "CB1") (pin "168") (pinfunction "168_168") (pintype "passive"))
      (node (ref "CB1") (pin "17") (pinfunction "17_17") (pintype "passive"))
      (node (ref "CB1") (pin "170") (pinfunction "170_170") (pintype "passive"))
      (node (ref "CB1") (pin "172") (pinfunction "172_172") (pintype "passive"))
      (node (ref "CB1") (pin "174") (pinfunction "174_174") (pintype "passive"))
      (node (ref "CB1") (pin "176") (pinfunction "176_176") (pintype "passive"))
      (node (ref "CB1") (pin "178") (pinfunction "178_178") (pintype "passive"))
      (node (ref "CB1") (pin "18") (pinfunction "18_18") (pintype "passive"))
      (node (ref "CB1") (pin "180") (pinfunction "180_180") (pintype "passive"))
      (node (ref "CB1") (pin "182") (pinfunction "182_182") (pintype "passive"))
      (node (ref "CB1") (pin "183") (pinfunction "183_183") (pintype "passive"))
      (node (ref "CB1") (pin "184") (pinfunction "184_184") (pintype "passive"))
      (node (ref "CB1") (pin "185") (pinfunction "185_185") (pintype "passive"))
      (node (ref "CB1") (pin "186") (pinfunction "186_186") (pintype "passive"))
      (node (ref "CB1") (pin "188") (pinfunction "188_188") (pintype "passive"))
      (node (ref "CB1") (pin "19") (pinfunction "19_19") (pintype "passive"))
      (node (ref "CB1") (pin "190") (pinfunction "190_190") (pintype "passive"))
      (node (ref "CB1") (pin "192") (pinfunction "192_192") (pintype "passive"))
      (node (ref "CB1") (pin "194") (pinfunction "194_194") (pintype "passive"))
      (node (ref "CB1") (pin "196") (pinfunction "196_196") (pintype "passive"))
      (node (ref "CB1") (pin "198") (pinfunction "198_198") (pintype "passive"))
      (node (ref "CB1") (pin "2") (pinfunction "2_2") (pintype "passive"))
      (node (ref "CB1") (pin "20") (pinfunction "20_20") (pintype "passive"))
      (node (ref "CB1") (pin "200") (pinfunction "200_200") (pintype "passive"))
      (node (ref "CB1") (pin "202") (pinfunction "202_202") (pintype "passive"))
      (node (ref "CB1") (pin "204") (pinfunction "204_204") (pintype "passive"))
      (node (ref "CB1") (pin "206") (pinfunction "206_206") (pintype "passive"))
      (node (ref "CB1") (pin "207") (pinfunction "207_207") (pintype "passive"))
      (node (ref "CB1") (pin "208") (pinfunction "208_208") (pintype "passive"))
      (node (ref "CB1") (pin "209") (pinfunction "209_209") (pintype "passive"))
      (node (ref "CB1") (pin "21") (pinfunction "21_21") (pintype "passive"))
      (node (ref "CB1") (pin "210") (pinfunction "210_210") (pintype "passive"))
      (node (ref "CB1") (pin "212") (pinfunction "212_212") (pintype "passive"))
      (node (ref "CB1") (pin "214") (pinfunction "214_214") (pintype "passive"))
      (node (ref "CB1") (pin "216") (pinfunction "216_216") (pintype "passive"))
      (node (ref "CB1") (pin "218") (pinfunction "218_218") (pintype "passive"))
      (node (ref "CB1") (pin "22") (pinfunction "22_22") (pintype "passive"))
      (node (ref "CB1") (pin "220") (pinfunction "220_220") (pintype "passive"))
      (node (ref "CB1") (pin "222") (pinfunction "222_222") (pintype "passive"))
      (node (ref "CB1") (pin "224") (pinfunction "224_224") (pintype "passive"))
      (node (ref "CB1") (pin "226") (pinfunction "226_226") (pintype "passive"))
      (node (ref "CB1") (pin "228") (pinfunction "228_228") (pintype "passive"))
      (node (ref "CB1") (pin "229") (pinfunction "229_229") (pintype "passive"))
      (node (ref "CB1") (pin "23") (pinfunction "23_23") (pintype "passive"))
      (node (ref "CB1") (pin "230") (pinfunction "230_230") (pintype "passive"))
      (node (ref "CB1") (pin "231") (pinfunction "231_231") (pintype "passive"))
      (node (ref "CB1") (pin "232") (pinfunction "232_232") (pintype "passive"))
      (node (ref "CB1") (pin "234") (pinfunction "234_234") (pintype "passive"))
      (node (ref "CB1") (pin "236") (pinfunction "236_236") (pintype "passive"))
      (node (ref "CB1") (pin "238") (pinfunction "238_238") (pintype "passive"))
      (node (ref "CB1") (pin "24") (pinfunction "24_24") (pintype "passive"))
      (node (ref "CB1") (pin "240") (pinfunction "240_240") (pintype "passive"))
      (node (ref "CB1") (pin "242") (pinfunction "242_242") (pintype "passive"))
      (node (ref "CB1") (pin "244") (pinfunction "244_244") (pintype "passive"))
      (node (ref "CB1") (pin "246") (pinfunction "246_246") (pintype "passive"))
      (node (ref "CB1") (pin "248") (pinfunction "248_248") (pintype "passive"))
      (node (ref "CB1") (pin "25") (pinfunction "25_25") (pintype "passive"))
      (node (ref "CB1") (pin "250") (pinfunction "250_250") (pintype "passive"))
      (node (ref "CB1") (pin "252") (pinfunction "252_252") (pintype "passive"))
      (node (ref "CB1") (pin "253") (pinfunction "253_253") (pintype "passive"))
      (node (ref "CB1") (pin "254") (pinfunction "254_254") (pintype "passive"))
      (node (ref "CB1") (pin "255") (pinfunction "255_255") (pintype "passive"))
      (node (ref "CB1") (pin "256") (pinfunction "256_256") (pintype "passive"))
      (node (ref "CB1") (pin "258") (pinfunction "258_258") (pintype "passive"))
      (node (ref "CB1") (pin "26") (pinfunction "26_26") (pintype "passive"))
      (node (ref "CB1") (pin "260") (pinfunction "260_260") (pintype "passive"))
      (node (ref "CB1") (pin "262") (pinfunction "262_262") (pintype "passive"))
      (node (ref "CB1") (pin "264") (pinfunction "264_264") (pintype "passive"))
      (node (ref "CB1") (pin "266") (pinfunction "266_266") (pintype "passive"))
      (node (ref "CB1") (pin "268") (pinfunction "268_268") (pintype "passive"))
      (node (ref "CB1") (pin "27") (pinfunction "27_27") (pintype "passive"))
      (node (ref "CB1") (pin "270") (pinfunction "270_270") (pintype "passive"))
      (node (ref "CB1") (pin "272") (pinfunction "272_272") (pintype "passive"))
      (node (ref "CB1") (pin "274") (pinfunction "274_274") (pintype "passive"))
      (node (ref "CB1") (pin "275") (pinfunction "275_275") (pintype "passive"))
      (node (ref "CB1") (pin "276") (pinfunction "276_276") (pintype "passive"))
      (node (ref "CB1") (pin "277") (pinfunction "277_277") (pintype "passive"))
      (node (ref "CB1") (pin "278") (pinfunction "278_278") (pintype "passive"))
      (node (ref "CB1") (pin "28") (pinfunction "28_28") (pintype "passive"))
      (node (ref "CB1") (pin "280") (pinfunction "280_280") (pintype "passive"))
      (node (ref "CB1") (pin "282") (pinfunction "282_282") (pintype "passive"))
      (node (ref "CB1") (pin "284") (pinfunction "284_284") (pintype "passive"))
      (node (ref "CB1") (pin "286") (pinfunction "286_286") (pintype "passive"))
      (node (ref "CB1") (pin "288") (pinfunction "288_288") (pintype "passive"))
      (node (ref "CB1") (pin "29") (pinfunction "29_29") (pintype "passive"))
      (node (ref "CB1") (pin "290") (pinfunction "290_290") (pintype "passive"))
      (node (ref "CB1") (pin "292") (pinfunction "292_292") (pintype "passive"))
      (node (ref "CB1") (pin "294") (pinfunction "294_294") (pintype "passive"))
      (node (ref "CB1") (pin "296") (pinfunction "296_296") (pintype "passive"))
      (node (ref "CB1") (pin "298") (pinfunction "298_298") (pintype "passive"))
      (node (ref "CB1") (pin "299") (pinfunction "299_299") (pintype "passive"))
      (node (ref "CB1") (pin "3") (pinfunction "3_3") (pintype "passive"))
      (node (ref "CB1") (pin "30") (pinfunction "30_30") (pintype "passive"))
      (node (ref "CB1") (pin "300") (pinfunction "300_300") (pintype "passive"))
      (node (ref "CB1") (pin "301") (pinfunction "301_301") (pintype "passive"))
      (node (ref "CB1") (pin "302") (pinfunction "302_302") (pintype "passive"))
      (node (ref "CB1") (pin "304") (pinfunction "304_304") (pintype "passive"))
      (node (ref "CB1") (pin "306") (pinfunction "306_306") (pintype "passive"))
      (node (ref "CB1") (pin "308") (pinfunction "308_308") (pintype "passive"))
      (node (ref "CB1") (pin "31") (pinfunction "31_31") (pintype "passive"))
      (node (ref "CB1") (pin "310") (pinfunction "310_310") (pintype "passive"))
      (node (ref "CB1") (pin "312") (pinfunction "312_312") (pintype "passive"))
      (node (ref "CB1") (pin "314") (pinfunction "314_314") (pintype "passive"))
      (node (ref "CB1") (pin "316") (pinfunction "316_316") (pintype "passive"))
      (node (ref "CB1") (pin "318") (pinfunction "318_318") (pintype "passive"))
      (node (ref "CB1") (pin "32") (pinfunction "32_32") (pintype "passive"))
      (node (ref "CB1") (pin "320") (pinfunction "320_320") (pintype "passive"))
      (node (ref "CB1") (pin "321") (pinfunction "321_321") (pintype "passive"))
      (node (ref "CB1") (pin "322") (pinfunction "322_322") (pintype "passive"))
      (node (ref "CB1") (pin "323") (pinfunction "323_323") (pintype "passive"))
      (node (ref "CB1") (pin "324") (pinfunction "324_324") (pintype "passive"))
      (node (ref "CB1") (pin "326") (pinfunction "326_326") (pintype "passive"))
      (node (ref "CB1") (pin "328") (pinfunction "328_328") (pintype "passive"))
      (node (ref "CB1") (pin "33") (pinfunction "33_33") (pintype "passive"))
      (node (ref "CB1") (pin "330") (pinfunction "330_330") (pintype "passive"))
      (node (ref "CB1") (pin "332") (pinfunction "332_332") (pintype "passive"))
      (node (ref "CB1") (pin "334") (pinfunction "334_334") (pintype "passive"))
      (node (ref "CB1") (pin "336") (pinfunction "336_336") (pintype "passive"))
      (node (ref "CB1") (pin "338") (pinfunction "338_338") (pintype "passive"))
      (node (ref "CB1") (pin "34") (pinfunction "34_34") (pintype "passive"))
      (node (ref "CB1") (pin "340") (pinfunction "340_340") (pintype "passive"))
      (node (ref "CB1") (pin "342") (pinfunction "342_342") (pintype "passive"))
      (node (ref "CB1") (pin "344") (pinfunction "344_344") (pintype "passive"))
      (node (ref "CB1") (pin "345") (pinfunction "345_345") (pintype "passive"))
      (node (ref "CB1") (pin "346") (pinfunction "346_346") (pintype "passive"))
      (node (ref "CB1") (pin "347") (pinfunction "347_347") (pintype "passive"))
      (node (ref "CB1") (pin "348") (pinfunction "348_348") (pintype "passive"))
      (node (ref "CB1") (pin "35") (pinfunction "35_35") (pintype "passive"))
      (node (ref "CB1") (pin "350") (pinfunction "350_350") (pintype "passive"))
      (node (ref "CB1") (pin "352") (pinfunction "352_352") (pintype "passive"))
      (node (ref "CB1") (pin "354") (pinfunction "354_354") (pintype "passive"))
      (node (ref "CB1") (pin "356") (pinfunction "356_356") (pintype "passive"))
      (node (ref "CB1") (pin "358") (pinfunction "358_358") (pintype "passive"))
      (node (ref "CB1") (pin "36") (pinfunction "36_36") (pintype "passive"))
      (node (ref "CB1") (pin "360") (pinfunction "360_360") (pintype "passive"))
      (node (ref "CB1") (pin "362") (pinfunction "362_362") (pintype "passive"))
      (node (ref "CB1") (pin "364") (pinfunction "364_364") (pintype "passive"))
      (node (ref "CB1") (pin "366") (pinfunction "366_366") (pintype "passive"))
      (node (ref "CB1") (pin "367") (pinfunction "367_367") (pintype "passive"))
      (node (ref "CB1") (pin "368") (pinfunction "368_368") (pintype "passive"))
      (node (ref "CB1") (pin "369") (pinfunction "369_369") (pintype "passive"))
      (node (ref "CB1") (pin "37") (pinfunction "37_37") (pintype "passive"))
      (node (ref "CB1") (pin "370") (pinfunction "370_370") (pintype "passive"))
      (node (ref "CB1") (pin "372") (pinfunction "372_372") (pintype "passive"))
      (node (ref "CB1") (pin "374") (pinfunction "374_374") (pintype "passive"))
      (node (ref "CB1") (pin "376") (pinfunction "376_376") (pintype "passive"))
      (node (ref "CB1") (pin "378") (pinfunction "378_378") (pintype "passive"))
      (node (ref "CB1") (pin "38") (pinfunction "38_38") (pintype "passive"))
      (node (ref "CB1") (pin "380") (pinfunction "380_380") (pintype "passive"))
      (node (ref "CB1") (pin "382") (pinfunction "382_382") (pintype "passive"))
      (node (ref "CB1") (pin "384") (pinfunction "384_384") (pintype "passive"))
      (node (ref "CB1") (pin "386") (pinfunction "386_386") (pintype "passive"))
      (node (ref "CB1") (pin "388") (pinfunction "388_388") (pintype "passive"))
      (node (ref "CB1") (pin "39") (pinfunction "39_39") (pintype "passive"))
      (node (ref "CB1") (pin "390") (pinfunction "390_390") (pintype "passive"))
      (node (ref "CB1") (pin "391") (pinfunction "391_391") (pintype "passive"))
      (node (ref "CB1") (pin "392") (pinfunction "392_392") (pintype "passive"))
      (node (ref "CB1") (pin "393") (pinfunction "393_393") (pintype "passive"))
      (node (ref "CB1") (pin "394") (pinfunction "394_394") (pintype "passive"))
      (node (ref "CB1") (pin "396") (pinfunction "396_396") (pintype "passive"))
      (node (ref "CB1") (pin "398") (pinfunction "398_398") (pintype "passive"))
      (node (ref "CB1") (pin "4") (pinfunction "4_4") (pintype "passive"))
      (node (ref "CB1") (pin "40") (pinfunction "40_40") (pintype "passive"))
      (node (ref "CB1") (pin "400") (pinfunction "400_400") (pintype "passive"))
      (node (ref "CB1") (pin "402") (pinfunction "402_402") (pintype "passive"))
      (node (ref "CB1") (pin "404") (pinfunction "404_404") (pintype "passive"))
      (node (ref "CB1") (pin "406") (pinfunction "406_406") (pintype "passive"))
      (node (ref "CB1") (pin "408") (pinfunction "408_408") (pintype "passive"))
      (node (ref "CB1") (pin "41") (pinfunction "41_41") (pintype "passive"))
      (node (ref "CB1") (pin "410") (pinfunction "410_410") (pintype "passive"))
      (node (ref "CB1") (pin "412") (pinfunction "412_412") (pintype "passive"))
      (node (ref "CB1") (pin "413") (pinfunction "413_413") (pintype "passive"))
      (node (ref "CB1") (pin "414") (pinfunction "414_414") (pintype "passive"))
      (node (ref "CB1") (pin "415") (pinfunction "415_415") (pintype "passive"))
      (node (ref "CB1") (pin "416") (pinfunction "416_416") (pintype "passive"))
      (node (ref "CB1") (pin "418") (pinfunction "418_418") (pintype "passive"))
      (node (ref "CB1") (pin "42") (pinfunction "42_42") (pintype "passive"))
      (node (ref "CB1") (pin "420") (pinfunction "420_420") (pintype "passive"))
      (node (ref "CB1") (pin "422") (pinfunction "422_422") (pintype "passive"))
      (node (ref "CB1") (pin "424") (pinfunction "424_424") (pintype "passive"))
      (node (ref "CB1") (pin "426") (pinfunction "426_426") (pintype "passive"))
      (node (ref "CB1") (pin "428") (pinfunction "428_428") (pintype "passive"))
      (node (ref "CB1") (pin "43") (pinfunction "43_43") (pintype "passive"))
      (node (ref "CB1") (pin "430") (pinfunction "430_430") (pintype "passive"))
      (node (ref "CB1") (pin "432") (pinfunction "432_432") (pintype "passive"))
      (node (ref "CB1") (pin "434") (pinfunction "434_434") (pintype "passive"))
      (node (ref "CB1") (pin "435") (pinfunction "435_435") (pintype "passive"))
      (node (ref "CB1") (pin "436") (pinfunction "436_436") (pintype "passive"))
      (node (ref "CB1") (pin "437") (pinfunction "437_437") (pintype "passive"))
      (node (ref "CB1") (pin "438") (pinfunction "438_438") (pintype "passive"))
      (node (ref "CB1") (pin "439") (pinfunction "439_439") (pintype "passive"))
      (node (ref "CB1") (pin "44") (pinfunction "44_44") (pintype "passive"))
      (node (ref "CB1") (pin "440") (pinfunction "440_440") (pintype "passive"))
      (node (ref "CB1") (pin "442") (pinfunction "442_442") (pintype "passive"))
      (node (ref "CB1") (pin "444") (pinfunction "444_444") (pintype "passive"))
      (node (ref "CB1") (pin "446") (pinfunction "446_446") (pintype "passive"))
      (node (ref "CB1") (pin "448") (pinfunction "448_448") (pintype "passive"))
      (node (ref "CB1") (pin "45") (pinfunction "45_45") (pintype "passive"))
      (node (ref "CB1") (pin "450") (pinfunction "450_450") (pintype "passive"))
      (node (ref "CB1") (pin "452") (pinfunction "452_452") (pintype "passive"))
      (node (ref "CB1") (pin "454") (pinfunction "454_454") (pintype "passive"))
      (node (ref "CB1") (pin "456") (pinfunction "456_456") (pintype "passive"))
      (node (ref "CB1") (pin "458") (pinfunction "458_458") (pintype "passive"))
      (node (ref "CB1") (pin "459") (pinfunction "459_459") (pintype "passive"))
      (node (ref "CB1") (pin "46") (pinfunction "46_46") (pintype "passive"))
      (node (ref "CB1") (pin "460") (pinfunction "460_460") (pintype "passive"))
      (node (ref "CB1") (pin "461") (pinfunction "461_461") (pintype "passive"))
      (node (ref "CB1") (pin "462") (pinfunction "462_462") (pintype "passive"))
      (node (ref "CB1") (pin "463") (pinfunction "463_463") (pintype "passive"))
      (node (ref "CB1") (pin "464") (pinfunction "464_464") (pintype "passive"))
      (node (ref "CB1") (pin "465") (pinfunction "465_465") (pintype "passive"))
      (node (ref "CB1") (pin "466") (pinfunction "466_466") (pintype "passive"))
      (node (ref "CB1") (pin "467") (pinfunction "467_467") (pintype "passive"))
      (node (ref "CB1") (pin "468") (pinfunction "468_468") (pintype "passive"))
      (node (ref "CB1") (pin "469") (pinfunction "469_469") (pintype "passive"))
      (node (ref "CB1") (pin "47") (pinfunction "47_47") (pintype "passive"))
      (node (ref "CB1") (pin "470") (pinfunction "470_470") (pintype "passive"))
      (node (ref "CB1") (pin "471") (pinfunction "471_471") (pintype "passive"))
      (node (ref "CB1") (pin "472") (pinfunction "472_472") (pintype "passive"))
      (node (ref "CB1") (pin "473") (pinfunction "473_473") (pintype "passive"))
      (node (ref "CB1") (pin "474") (pinfunction "474_474") (pintype "passive"))
      (node (ref "CB1") (pin "475") (pinfunction "475_475") (pintype "passive"))
      (node (ref "CB1") (pin "476") (pinfunction "476_476") (pintype "passive"))
      (node (ref "CB1") (pin "477") (pinfunction "477_477") (pintype "passive"))
      (node (ref "CB1") (pin "478") (pinfunction "478_478") (pintype "passive"))
      (node (ref "CB1") (pin "479") (pinfunction "479_479") (pintype "passive"))
      (node (ref "CB1") (pin "48") (pinfunction "48_48") (pintype "passive"))
      (node (ref "CB1") (pin "480") (pinfunction "480_480") (pintype "passive"))
      (node (ref "CB1") (pin "481") (pinfunction "481_481") (pintype "passive"))
      (node (ref "CB1") (pin "482") (pinfunction "482_482") (pintype "passive"))
      (node (ref "CB1") (pin "483") (pinfunction "483_483") (pintype "passive"))
      (node (ref "CB1") (pin "484") (pinfunction "484_484") (pintype "passive"))
      (node (ref "CB1") (pin "485") (pinfunction "485_485") (pintype "passive"))
      (node (ref "CB1") (pin "486") (pinfunction "486_486") (pintype "passive"))
      (node (ref "CB1") (pin "487") (pinfunction "487_487") (pintype "passive"))
      (node (ref "CB1") (pin "488") (pinfunction "488_488") (pintype "passive"))
      (node (ref "CB1") (pin "489") (pinfunction "489_489") (pintype "passive"))
      (node (ref "CB1") (pin "49") (pinfunction "49_49") (pintype "passive"))
      (node (ref "CB1") (pin "490") (pinfunction "490_490") (pintype "passive"))
      (node (ref "CB1") (pin "491") (pinfunction "491_491") (pintype "passive"))
      (node (ref "CB1") (pin "492") (pinfunction "492_492") (pintype "passive"))
      (node (ref "CB1") (pin "493") (pinfunction "493_493") (pintype "passive"))
      (node (ref "CB1") (pin "494") (pinfunction "494_494") (pintype "passive"))
      (node (ref "CB1") (pin "495") (pinfunction "495_495") (pintype "passive"))
      (node (ref "CB1") (pin "496") (pinfunction "496_496") (pintype "passive"))
      (node (ref "CB1") (pin "497") (pinfunction "497_497") (pintype "passive"))
      (node (ref "CB1") (pin "498") (pinfunction "498_498") (pintype "passive"))
      (node (ref "CB1") (pin "499") (pinfunction "499_499") (pintype "passive"))
      (node (ref "CB1") (pin "5") (pinfunction "5_5") (pintype "passive"))
      (node (ref "CB1") (pin "50") (pinfunction "50_50") (pintype "passive"))
      (node (ref "CB1") (pin "500") (pinfunction "500_500") (pintype "passive"))
      (node (ref "CB1") (pin "501") (pinfunction "501_501") (pintype "passive"))
      (node (ref "CB1") (pin "502") (pinfunction "502_502") (pintype "passive"))
      (node (ref "CB1") (pin "503") (pinfunction "503_503") (pintype "passive"))
      (node (ref "CB1") (pin "504") (pinfunction "504_504") (pintype "passive"))
      (node (ref "CB1") (pin "505") (pinfunction "505_505") (pintype "passive"))
      (node (ref "CB1") (pin "506") (pinfunction "506_506") (pintype "passive"))
      (node (ref "CB1") (pin "507") (pinfunction "507_507") (pintype "passive"))
      (node (ref "CB1") (pin "508") (pinfunction "508_508") (pintype "passive"))
      (node (ref "CB1") (pin "509") (pinfunction "509_509") (pintype "passive"))
      (node (ref "CB1") (pin "51") (pinfunction "51_51") (pintype "passive"))
      (node (ref "CB1") (pin "510") (pinfunction "510_510") (pintype "passive"))
      (node (ref "CB1") (pin "511") (pinfunction "511_511") (pintype "passive"))
      (node (ref "CB1") (pin "512") (pinfunction "512_512") (pintype "passive"))
      (node (ref "CB1") (pin "513") (pinfunction "513_513") (pintype "passive"))
      (node (ref "CB1") (pin "514") (pinfunction "514_514") (pintype "passive"))
      (node (ref "CB1") (pin "515") (pinfunction "515_515") (pintype "passive"))
      (node (ref "CB1") (pin "516") (pinfunction "516_516") (pintype "passive"))
      (node (ref "CB1") (pin "517") (pinfunction "517_517") (pintype "passive"))
      (node (ref "CB1") (pin "518") (pinfunction "518_518") (pintype "passive"))
      (node (ref "CB1") (pin "519") (pinfunction "519_519") (pintype "passive"))
      (node (ref "CB1") (pin "52") (pinfunction "52_52") (pintype "passive"))
      (node (ref "CB1") (pin "520") (pinfunction "520_520") (pintype "passive"))
      (node (ref "CB1") (pin "521") (pinfunction "521_521") (pintype "passive"))
      (node (ref "CB1") (pin "522") (pinfunction "522_522") (pintype "passive"))
      (node (ref "CB1") (pin "523") (pinfunction "523_523") (pintype "passive"))
      (node (ref "CB1") (pin "524") (pinfunction "524_524") (pintype "passive"))
      (node (ref "CB1") (pin "525") (pinfunction "525_525") (pintype "passive"))
      (node (ref "CB1") (pin "526") (pinfunction "526_526") (pintype "passive"))
      (node (ref "CB1") (pin "527") (pinfunction "527_527") (pintype "passive"))
      (node (ref "CB1") (pin "528") (pinfunction "528_528") (pintype "passive"))
      (node (ref "CB1") (pin "529") (pinfunction "529_529") (pintype "passive"))
      (node (ref "CB1") (pin "53") (pinfunction "53_53") (pintype "passive"))
      (node (ref "CB1") (pin "54") (pinfunction "54_54") (pintype "passive"))
      (node (ref "CB1") (pin "55") (pinfunction "55_55") (pintype "passive"))
      (node (ref "CB1") (pin "56") (pinfunction "56_56") (pintype "passive"))
      (node (ref "CB1") (pin "57") (pinfunction "57_57") (pintype "passive"))
      (node (ref "CB1") (pin "58") (pinfunction "58_58") (pintype "passive"))
      (node (ref "CB1") (pin "59") (pinfunction "59_59") (pintype "passive"))
      (node (ref "CB1") (pin "6") (pinfunction "6_6") (pintype "passive"))
      (node (ref "CB1") (pin "60") (pinfunction "60_60") (pintype "passive"))
      (node (ref "CB1") (pin "61") (pinfunction "61_61") (pintype "passive"))
      (node (ref "CB1") (pin "62") (pinfunction "62_62") (pintype "passive"))
      (node (ref "CB1") (pin "63") (pinfunction "63_63") (pintype "passive"))
      (node (ref "CB1") (pin "64") (pinfunction "64_64") (pintype "passive"))
      (node (ref "CB1") (pin "65") (pinfunction "65_65") (pintype "passive"))
      (node (ref "CB1") (pin "66") (pinfunction "66_66") (pintype "passive"))
      (node (ref "CB1") (pin "67") (pinfunction "67_67") (pintype "passive"))
      (node (ref "CB1") (pin "68") (pinfunction "68_68") (pintype "passive"))
      (node (ref "CB1") (pin "69") (pinfunction "69_69") (pintype "passive"))
      (node (ref "CB1") (pin "7") (pinfunction "7_7") (pintype "passive"))
      (node (ref "CB1") (pin "70") (pinfunction "70_70") (pintype "passive"))
      (node (ref "CB1") (pin "71") (pinfunction "71_71") (pintype "passive"))
      (node (ref "CB1") (pin "72") (pinfunction "72_72") (pintype "passive"))
      (node (ref "CB1") (pin "74") (pinfunction "74_74") (pintype "passive"))
      (node (ref "CB1") (pin "76") (pinfunction "76_76") (pintype "passive"))
      (node (ref "CB1") (pin "78") (pinfunction "78_78") (pintype "passive"))
      (node (ref "CB1") (pin "8") (pinfunction "8_8") (pintype "passive"))
      (node (ref "CB1") (pin "80") (pinfunction "80_80") (pintype "passive"))
      (node (ref "CB1") (pin "82") (pinfunction "82_82") (pintype "passive"))
      (node (ref "CB1") (pin "84") (pinfunction "84_84") (pintype "passive"))
      (node (ref "CB1") (pin "86") (pinfunction "86_86") (pintype "passive"))
      (node (ref "CB1") (pin "88") (pinfunction "88_88") (pintype "passive"))
      (node (ref "CB1") (pin "9") (pinfunction "9_9") (pintype "passive"))
      (node (ref "CB1") (pin "90") (pinfunction "90_90") (pintype "passive"))
      (node (ref "CB1") (pin "91") (pinfunction "91_91") (pintype "passive"))
      (node (ref "CB1") (pin "92") (pinfunction "92_92") (pintype "passive"))
      (node (ref "CB1") (pin "93") (pinfunction "93_93") (pintype "passive"))
      (node (ref "CB1") (pin "94") (pinfunction "94_94") (pintype "passive"))
      (node (ref "CB1") (pin "96") (pinfunction "96_96") (pintype "passive"))
      (node (ref "CB1") (pin "98") (pinfunction "98_98") (pintype "passive"))
      (node (ref "J1") (pin "180") (pinfunction "180_180") (pintype "passive"))
      (node (ref "J1") (pin "181") (pinfunction "181_181") (pintype "passive"))
      (node (ref "J1") (pin "182") (pinfunction "182_182") (pintype "passive"))
      (node (ref "J1") (pin "183") (pinfunction "183_183") (pintype "passive"))
      (node (ref "J1") (pin "184") (pinfunction "184_184") (pintype "passive"))
      (node (ref "J1") (pin "185") (pinfunction "185_185") (pintype "passive"))
      (node (ref "J1") (pin "186") (pinfunction "186_186") (pintype "passive"))
      (node (ref "J1") (pin "187") (pinfunction "187_187") (pintype "passive"))
      (node (ref "J1") (pin "188") (pinfunction "188_188") (pintype "passive"))
      (node (ref "J1") (pin "189") (pinfunction "189_189") (pintype "passive"))
      (node (ref "J1") (pin "190") (pinfunction "190_190") (pintype "passive"))
      (node (ref "J1") (pin "191") (pinfunction "191_191") (pintype "passive"))
      (node (ref "J1") (pin "192") (pinfunction "192_192") (pintype "passive"))
      (node (ref "J2") (pin "180") (pinfunction "180_180") (pintype "passive"))
      (node (ref "J2") (pin "181") (pinfunction "181_181") (pintype "passive"))
      (node (ref "J2") (pin "182") (pinfunction "182_182") (pintype "passive"))
      (node (ref "J2") (pin "183") (pinfunction "183_183") (pintype "passive"))
      (node (ref "J2") (pin "184") (pinfunction "184_184") (pintype "passive"))
      (node (ref "J2") (pin "185") (pinfunction "185_185") (pintype "passive"))
      (node (ref "J2") (pin "186") (pinfunction "186_186") (pintype "passive"))
      (node (ref "J2") (pin "187") (pinfunction "187_187") (pintype "passive"))
      (node (ref "J2") (pin "188") (pinfunction "188_188") (pintype "passive"))
      (node (ref "J2") (pin "189") (pinfunction "189_189") (pintype "passive"))
      (node (ref "J2") (pin "190") (pinfunction "190_190") (pintype "passive"))
      (node (ref "J2") (pin "191") (pinfunction "191_191") (pintype "passive"))
      (node (ref "J2") (pin "192") (pinfunction "192_192") (pintype "passive"))
      (node (ref "P1") (pin "10") (pinfunction "10_10") (pintype "passive"))
      (node (ref "P1") (pin "2") (pinfunction "2_2") (pintype "passive"))
      (node (ref "P2") (pin "2") (pinfunction "1_2") (pintype "passive"))
      (node (ref "P2") (pin "3") (pinfunction "2_3") (pintype "passive"))
      (node (ref "P2") (pin "4") (pinfunction "3_4") (pintype "passive"))
      (node (ref "P2") (pin "5") (pinfunction "4_5") (pintype "passive"))
      (node (ref "P3") (pin "2") (pinfunction "1_2") (pintype "passive"))
      (node (ref "P3") (pin "3") (pinfunction "2_3") (pintype "passive"))
      (node (ref "P3") (pin "4") (pinfunction "3_4") (pintype "passive"))
      (node (ref "P3") (pin "5") (pinfunction "4_5") (pintype "passive"))
      (node (ref "R1") (pin "1") (pinfunction "1_1") (pintype "passive"))
      (node (ref "R2") (pin "1") (pinfunction "1_1") (pintype "passive"))
      (node (ref "TP6") (pin "0") (pinfunction "0_0") (pintype "passive"))
      (node (ref "TP7") (pin "0") (pinfunction "0_0") (pintype "passive"))
      (node (ref "TP8") (pin "0") (pinfunction "0_0") (pintype "passive"))
      (node (ref "TP9") (pin "0") (pinfunction "0_0") (pintype "passive"))
    )
    (net (code "172") (name "unconnected-(J1-Pad1)") (class "Default")
      (node (ref "J1") (pin "1") (pinfunction "1_1") (pintype "passive+no_connect"))
    )
    (net (code "173") (name "unconnected-(J1-Pad2)") (class "Default")
      (node (ref "J1") (pin "2") (pinfunction "2_2") (pintype "passive+no_connect"))
    )
    (net (code "174") (name "unconnected-(J1-Pad3)") (class "Default")
      (node (ref "J1") (pin "3") (pinfunction "3_3") (pintype "passive+no_connect"))
    )
    (net (code "175") (name "unconnected-(J1-Pad4)") (class "Default")
      (node (ref "J1") (pin "4") (pinfunction "4_4") (pintype "passive+no_connect"))
    )
    (net (code "176") (name "unconnected-(J1-Pad5)") (class "Default")
      (node (ref "J1") (pin "5") (pinfunction "5_5") (pintype "passive+no_connect"))
    )
    (net (code "177") (name "unconnected-(J1-Pad7)") (class "Default")
      (node (ref "J1") (pin "7") (pinfunction "7_7") (pintype "passive+no_connect"))
    )
    (net (code "178") (name "unconnected-(J1-Pad8)") (class "Default")
      (node (ref "J1") (pin "8") (pinfunction "8_8") (pintype "passive+no_connect"))
    )
    (net (code "179") (name "unconnected-(J1-Pad9)") (class "Default")
      (node (ref "J1") (pin "9") (pinfunction "9_9") (pintype "passive+no_connect"))
    )
    (net (code "180") (name "unconnected-(J1-Pad10)") (class "Default")
      (node (ref "J1") (pin "10") (pinfunction "10_10") (pintype "passive+no_connect"))
    )
    (net (code "181") (name "unconnected-(J1-Pad11)") (class "Default")
      (node (ref "J1") (pin "11") (pinfunction "11_11") (pintype "passive+no_connect"))
    )
    (net (code "182") (name "unconnected-(J1-Pad13)") (class "Default")
      (node (ref "J1") (pin "13") (pinfunction "13_13") (pintype "passive+no_connect"))
    )
    (net (code "183") (name "unconnected-(J1-Pad14)") (class "Default")
      (node (ref "J1") (pin "14") (pinfunction "14_14") (pintype "passive+no_connect"))
    )
    (net (code "184") (name "unconnected-(J1-Pad15)") (class "Default")
      (node (ref "J1") (pin "15") (pinfunction "15_15") (pintype "passive+no_connect"))
    )
    (net (code "185") (name "unconnected-(J1-Pad16)") (class "Default")
      (node (ref "J1") (pin "16") (pinfunction "16_16") (pintype "passive+no_connect"))
    )
    (net (code "186") (name "unconnected-(J1-Pad17)") (class "Default")
      (node (ref "J1") (pin "17") (pinfunction "17_17") (pintype "passive+no_connect"))
    )
    (net (code "187") (name "unconnected-(J1-Pad18)") (class "Default")
      (node (ref "J1") (pin "18") (pinfunction "18_18") (pintype "passive+no_connect"))
    )
    (net (code "188") (name "unconnected-(J1-Pad19)") (class "Default")
      (node (ref "J1") (pin "19") (pinfunction "19_19") (pintype "passive+no_connect"))
    )
    (net (code "189") (name "unconnected-(J1-Pad20)") (class "Default")
      (node (ref "J1") (pin "20") (pinfunction "20_20") (pintype "passive+no_connect"))
    )
    (net (code "190") (name "unconnected-(J1-Pad21)") (class "Default")
      (node (ref "J1") (pin "21") (pinfunction "21_21") (pintype "passive+no_connect"))
    )
    (net (code "191") (name "unconnected-(J1-Pad22)") (class "Default")
      (node (ref "J1") (pin "22") (pinfunction "22_22") (pintype "passive+no_connect"))
    )
    (net (code "192") (name "unconnected-(J1-Pad23)") (class "Default")
      (node (ref "J1") (pin "23") (pinfunction "23_23") (pintype "passive+no_connect"))
    )
    (net (code "193") (name "unconnected-(J1-Pad24)") (class "Default")
      (node (ref "J1") (pin "24") (pinfunction "24_24") (pintype "passive+no_connect"))
    )
    (net (code "194") (name "unconnected-(J1-Pad25)") (class "Default")
      (node (ref "J1") (pin "25") (pinfunction "25_25") (pintype "passive+no_connect"))
    )
    (net (code "195") (name "unconnected-(J1-Pad26)") (class "Default")
      (node (ref "J1") (pin "26") (pinfunction "26_26") (pintype "passive+no_connect"))
    )
    (net (code "196") (name "unconnected-(J1-Pad27)") (class "Default")
      (node (ref "J1") (pin "27") (pinfunction "27_27") (pintype "passive+no_connect"))
    )
    (net (code "197") (name "unconnected-(J1-Pad28)") (class "Default")
      (node (ref "J1") (pin "28") (pinfunction "28_28") (pintype "passive+no_connect"))
    )
    (net (code "198") (name "unconnected-(J1-Pad29)") (class "Default")
      (node (ref "J1") (pin "29") (pinfunction "29_29") (pintype "passive+no_connect"))
    )
    (net (code "199") (name "unconnected-(J1-Pad30)") (class "Default")
      (node (ref "J1") (pin "30") (pinfunction "30_30") (pintype "passive+no_connect"))
    )
    (net (code "200") (name "unconnected-(J1-Pad31)") (class "Default")
      (node (ref "J1") (pin "31") (pinfunction "31_31") (pintype "passive+no_connect"))
    )
    (net (code "201") (name "unconnected-(J1-Pad32)") (class "Default")
      (node (ref "J1") (pin "32") (pinfunction "32_32") (pintype "passive+no_connect"))
    )
    (net (code "202") (name "unconnected-(J1-Pad33)") (class "Default")
      (node (ref "J1") (pin "33") (pinfunction "33_33") (pintype "passive+no_connect"))
    )
    (net (code "203") (name "unconnected-(J1-Pad34)") (class "Default")
      (node (ref "J1") (pin "34") (pinfunction "34_34") (pintype "passive+no_connect"))
    )
    (net (code "204") (name "unconnected-(J1-Pad35)") (class "Default")
      (node (ref "J1") (pin "35") (pinfunction "35_35") (pintype "passive+no_connect"))
    )
    (net (code "205") (name "unconnected-(J1-Pad36)") (class "Default")
      (node (ref "J1") (pin "36") (pinfunction "36_36") (pintype "passive+no_connect"))
    )
    (net (code "206") (name "unconnected-(J1-Pad37)") (class "Default")
      (node (ref "J1") (pin "37") (pinfunction "37_37") (pintype "passive+no_connect"))
    )
    (net (code "207") (name "unconnected-(J1-Pad38)") (class "Default")
      (node (ref "J1") (pin "38") (pinfunction "38_38") (pintype "passive+no_connect"))
    )
    (net (code "208") (name "unconnected-(J1-Pad39)") (class "Default")
      (node (ref "J1") (pin "39") (pinfunction "39_39") (pintype "passive+no_connect"))
    )
    (net (code "209") (name "unconnected-(J1-Pad40)") (class "Default")
      (node (ref "J1") (pin "40") (pinfunction "40_40") (pintype "passive+no_connect"))
    )
    (net (code "210") (name "unconnected-(J1-Pad41)") (class "Default")
      (node (ref "J1") (pin "41") (pinfunction "41_41") (pintype "passive+no_connect"))
    )
    (net (code "211") (name "unconnected-(J1-Pad43)") (class "Default")
      (node (ref "J1") (pin "43") (pinfunction "43_43") (pintype "passive+no_connect"))
    )
    (net (code "212") (name "unconnected-(J1-Pad44)") (class "Default")
      (node (ref "J1") (pin "44") (pinfunction "44_44") (pintype "passive+no_connect"))
    )
    (net (code "213") (name "unconnected-(J1-Pad45)") (class "Default")
      (node (ref "J1") (pin "45") (pinfunction "45_45") (pintype "passive+no_connect"))
    )
    (net (code "214") (name "unconnected-(J1-Pad46)") (class "Default")
      (node (ref "J1") (pin "46") (pinfunction "46_46") (pintype "passive+no_connect"))
    )
    (net (code "215") (name "unconnected-(J1-Pad47)") (class "Default")
      (node (ref "J1") (pin "47") (pinfunction "47_47") (pintype "passive+no_connect"))
    )
    (net (code "216") (name "unconnected-(J1-Pad49)") (class "Default")
      (node (ref "J1") (pin "49") (pinfunction "49_49") (pintype "passive+no_connect"))
    )
    (net (code "217") (name "unconnected-(J1-Pad50)") (class "Default")
      (node (ref "J1") (pin "50") (pinfunction "50_50") (pintype "passive+no_connect"))
    )
    (net (code "218") (name "unconnected-(J1-Pad51)") (class "Default")
      (node (ref "J1") (pin "51") (pinfunction "51_51") (pintype "passive+no_connect"))
    )
    (net (code "219") (name "unconnected-(J1-Pad52)") (class "Default")
      (node (ref "J1") (pin "52") (pinfunction "52_52") (pintype "passive+no_connect"))
    )
    (net (code "220") (name "unconnected-(J1-Pad53)") (class "Default")
      (node (ref "J1") (pin "53") (pinfunction "53_53") (pintype "passive+no_connect"))
    )
    (net (code "221") (name "unconnected-(J1-Pad55)") (class "Default")
      (node (ref "J1") (pin "55") (pinfunction "55_55") (pintype "passive+no_connect"))
    )
    (net (code "222") (name "unconnected-(J1-Pad56)") (class "Default")
      (node (ref "J1") (pin "56") (pinfunction "56_56") (pintype "passive+no_connect"))
    )
    (net (code "223") (name "unconnected-(J1-Pad57)") (class "Default")
      (node (ref "J1") (pin "57") (pinfunction "57_57") (pintype "passive+no_connect"))
    )
    (net (code "224") (name "unconnected-(J1-Pad58)") (class "Default")
      (node (ref "J1") (pin "58") (pinfunction "58_58") (pintype "passive+no_connect"))
    )
    (net (code "225") (name "unconnected-(J1-Pad59)") (class "Default")
      (node (ref "J1") (pin "59") (pinfunction "59_59") (pintype "passive+no_connect"))
    )
    (net (code "226") (name "unconnected-(J2-Pad1)") (class "Default")
      (node (ref "J2") (pin "1") (pinfunction "1_1") (pintype "passive+no_connect"))
    )
    (net (code "227") (name "unconnected-(J2-Pad2)") (class "Default")
      (node (ref "J2") (pin "2") (pinfunction "2_2") (pintype "passive+no_connect"))
    )
    (net (code "228") (name "unconnected-(J2-Pad3)") (class "Default")
      (node (ref "J2") (pin "3") (pinfunction "3_3") (pintype "passive+no_connect"))
    )
    (net (code "229") (name "unconnected-(J2-Pad4)") (class "Default")
      (node (ref "J2") (pin "4") (pinfunction "4_4") (pintype "passive+no_connect"))
    )
    (net (code "230") (name "unconnected-(J2-Pad5)") (class "Default")
      (node (ref "J2") (pin "5") (pinfunction "5_5") (pintype "passive+no_connect"))
    )
    (net (code "231") (name "unconnected-(J2-Pad6)") (class "Default")
      (node (ref "J2") (pin "6") (pinfunction "6_6") (pintype "passive+no_connect"))
    )
    (net (code "232") (name "unconnected-(J2-Pad7)") (class "Default")
      (node (ref "J2") (pin "7") (pinfunction "7_7") (pintype "passive+no_connect"))
    )
    (net (code "233") (name "unconnected-(J2-Pad8)") (class "Default")
      (node (ref "J2") (pin "8") (pinfunction "8_8") (pintype "passive+no_connect"))
    )
    (net (code "234") (name "unconnected-(J2-Pad9)") (class "Default")
      (node (ref "J2") (pin "9") (pinfunction "9_9") (pintype "passive+no_connect"))
    )
    (net (code "235") (name "unconnected-(J2-Pad10)") (class "Default")
      (node (ref "J2") (pin "10") (pinfunction "10_10") (pintype "passive+no_connect"))
    )
    (net (code "236") (name "unconnected-(J2-Pad11)") (class "Default")
      (node (ref "J2") (pin "11") (pinfunction "11_11") (pintype "passive+no_connect"))
    )
    (net (code "237") (name "unconnected-(J2-Pad12)") (class "Default")
      (node (ref "J2") (pin "12") (pinfunction "12_12") (pintype "passive+no_connect"))
    )
    (net (code "238") (name "unconnected-(J2-Pad13)") (class "Default")
      (node (ref "J2") (pin "13") (pinfunction "13_13") (pintype "passive+no_connect"))
    )
    (net (code "239") (name "unconnected-(J2-Pad14)") (class "Default")
      (node (ref "J2") (pin "14") (pinfunction "14_14") (pintype "passive+no_connect"))
    )
    (net (code "240") (name "unconnected-(J2-Pad15)") (class "Default")
      (node (ref "J2") (pin "15") (pinfunction "15_15") (pintype "passive+no_connect"))
    )
    (net (code "241") (name "unconnected-(J2-Pad16)") (class "Default")
      (node (ref "J2") (pin "16") (pinfunction "16_16") (pintype "passive+no_connect"))
    )
    (net (code "242") (name "unconnected-(J2-Pad17)") (class "Default")
      (node (ref "J2") (pin "17") (pinfunction "17_17") (pintype "passive+no_connect"))
    )
    (net (code "243") (name "unconnected-(J2-Pad18)") (class "Default")
      (node (ref "J2") (pin "18") (pinfunction "18_18") (pintype "passive+no_connect"))
    )
    (net (code "244") (name "unconnected-(J2-Pad19)") (class "Default")
      (node (ref "J2") (pin "19") (pinfunction "19_19") (pintype "passive+no_connect"))
    )
    (net (code "245") (name "unconnected-(J2-Pad20)") (class "Default")
      (node (ref "J2") (pin "20") (pinfunction "20_20") (pintype "passive+no_connect"))
    )
    (net (code "246") (name "unconnected-(J2-Pad21)") (class "Default")
      (node (ref "J2") (pin "21") (pinfunction "21_21") (pintype "passive+no_connect"))
    )
    (net (code "247") (name "unconnected-(J2-Pad22)") (class "Default")
      (node (ref "J2") (pin "22") (pinfunction "22_22") (pintype "passive+no_connect"))
    )
    (net (code "248") (name "unconnected-(J2-Pad23)") (class "Default")
      (node (ref "J2") (pin "23") (pinfunction "23_23") (pintype "passive+no_connect"))
    )
    (net (code "249") (name "unconnected-(J2-Pad24)") (class "Default")
      (node (ref "J2") (pin "24") (pinfunction "24_24") (pintype "passive+no_connect"))
    )
    (net (code "250") (name "unconnected-(J2-Pad25)") (class "Default")
      (node (ref "J2") (pin "25") (pinfunction "25_25") (pintype "passive+no_connect"))
    )
    (net (code "251") (name "unconnected-(J2-Pad26)") (class "Default")
      (node (ref "J2") (pin "26") (pinfunction "26_26") (pintype "passive+no_connect"))
    )
    (net (code "252") (name "unconnected-(J2-Pad27)") (class "Default")
      (node (ref "J2") (pin "27") (pinfunction "27_27") (pintype "passive+no_connect"))
    )
    (net (code "253") (name "unconnected-(J2-Pad28)") (class "Default")
      (node (ref "J2") (pin "28") (pinfunction "28_28") (pintype "passive+no_connect"))
    )
    (net (code "254") (name "unconnected-(J2-Pad29)") (class "Default")
      (node (ref "J2") (pin "29") (pinfunction "29_29") (pintype "passive+no_connect"))
    )
    (net (code "255") (name "unconnected-(J2-Pad30)") (class "Default")
      (node (ref "J2") (pin "30") (pinfunction "30_30") (pintype "passive+no_connect"))
    )
    (net (code "256") (name "unconnected-(J2-Pad31)") (class "Default")
      (node (ref "J2") (pin "31") (pinfunction "31_31") (pintype "passive+no_connect"))
    )
    (net (code "257") (name "unconnected-(J2-Pad32)") (class "Default")
      (node (ref "J2") (pin "32") (pinfunction "32_32") (pintype "passive+no_connect"))
    )
    (net (code "258") (name "unconnected-(J2-Pad33)") (class "Default")
      (node (ref "J2") (pin "33") (pinfunction "33_33") (pintype "passive+no_connect"))
    )
    (net (code "259") (name "unconnected-(J2-Pad34)") (class "Default")
      (node (ref "J2") (pin "34") (pinfunction "34_34") (pintype "passive+no_connect"))
    )
    (net (code "260") (name "unconnected-(J2-Pad35)") (class "Default")
      (node (ref "J2") (pin "35") (pinfunction "35_35") (pintype "passive+no_connect"))
    )
    (net (code "261") (name "unconnected-(J2-Pad36)") (class "Default")
      (node (ref "J2") (pin "36") (pinfunction "36_36") (pintype "passive+no_connect"))
    )
    (net (code "262") (name "unconnected-(J2-Pad37)") (class "Default")
      (node (ref "J2") (pin "37") (pinfunction "37_37") (pintype "passive+no_connect"))
    )
    (net (code "263") (name "unconnected-(J2-Pad38)") (class "Default")
      (node (ref "J2") (pin "38") (pinfunction "38_38") (pintype "passive+no_connect"))
    )
    (net (code "264") (name "unconnected-(J2-Pad39)") (class "Default")
      (node (ref "J2") (pin "39") (pinfunction "39_39") (pintype "passive+no_connect"))
    )
    (net (code "265") (name "unconnected-(J2-Pad40)") (class "Default")
      (node (ref "J2") (pin "40") (pinfunction "40_40") (pintype "passive+no_connect"))
    )
    (net (code "266") (name "unconnected-(J2-Pad41)") (class "Default")
      (node (ref "J2") (pin "41") (pinfunction "41_41") (pintype "passive+no_connect"))
    )
    (net (code "267") (name "unconnected-(J2-Pad42)") (class "Default")
      (node (ref "J2") (pin "42") (pinfunction "42_42") (pintype "passive+no_connect"))
    )
    (net (code "268") (name "unconnected-(J2-Pad43)") (class "Default")
      (node (ref "J2") (pin "43") (pinfunction "43_43") (pintype "passive+no_connect"))
    )
    (net (code "269") (name "unconnected-(J2-Pad44)") (class "Default")
      (node (ref "J2") (pin "44") (pinfunction "44_44") (pintype "passive+no_connect"))
    )
    (net (code "270") (name "unconnected-(J2-Pad45)") (class "Default")
      (node (ref "J2") (pin "45") (pinfunction "45_45") (pintype "passive+no_connect"))
    )
    (net (code "271") (name "unconnected-(J2-Pad46)") (class "Default")
      (node (ref "J2") (pin "46") (pinfunction "46_46") (pintype "passive+no_connect"))
    )
    (net (code "272") (name "unconnected-(J2-Pad47)") (class "Default")
      (node (ref "J2") (pin "47") (pinfunction "47_47") (pintype "passive+no_connect"))
    )
    (net (code "273") (name "unconnected-(J2-Pad49)") (class "Default")
      (node (ref "J2") (pin "49") (pinfunction "49_49") (pintype "passive+no_connect"))
    )
    (net (code "274") (name "unconnected-(J2-Pad50)") (class "Default")
      (node (ref "J2") (pin "50") (pinfunction "50_50") (pintype "passive+no_connect"))
    )
    (net (code "275") (name "unconnected-(J2-Pad51)") (class "Default")
      (node (ref "J2") (pin "51") (pinfunction "51_51") (pintype "passive+no_connect"))
    )
    (net (code "276") (name "unconnected-(J2-Pad52)") (class "Default")
      (node (ref "J2") (pin "52") (pinfunction "52_52") (pintype "passive+no_connect"))
    )
    (net (code "277") (name "unconnected-(J2-Pad53)") (class "Default")
      (node (ref "J2") (pin "53") (pinfunction "53_53") (pintype "passive+no_connect"))
    )
    (net (code "278") (name "unconnected-(J2-Pad54)") (class "Default")
      (node (ref "J2") (pin "54") (pinfunction "54_54") (pintype "passive+no_connect"))
    )
    (net (code "279") (name "unconnected-(J2-Pad55)") (class "Default")
      (node (ref "J2") (pin "55") (pinfunction "55_55") (pintype "passive+no_connect"))
    )
    (net (code "280") (name "unconnected-(J2-Pad56)") (class "Default")
      (node (ref "J2") (pin "56") (pinfunction "56_56") (pintype "passive+no_connect"))
    )
    (net (code "281") (name "unconnected-(J2-Pad57)") (class "Default")
      (node (ref "J2") (pin "57") (pinfunction "57_57") (pintype "passive+no_connect"))
    )
    (net (code "282") (name "unconnected-(J2-Pad59)") (class "Default")
      (node (ref "J2") (pin "59") (pinfunction "59_59") (pintype "passive+no_connect"))
    )
    (net (code "283") (name "unconnected-(J2-Pad60)") (class "Default")
      (node (ref "J2") (pin "60") (pinfunction "60_60") (pintype "passive+no_connect"))
    )
    (net (code "284") (name "unconnected-(P1-Pad6)") (class "Default")
      (node (ref "P1") (pin "6") (pinfunction "6_6") (pintype "passive+no_connect"))
    )
    (net (code "285") (name "unconnected-(P1-Pad7)") (class "Default")
      (node (ref "P1") (pin "7") (pinfunction "7_7") (pintype "passive+no_connect"))
    )
    (net (code "286") (name "unconnected-(P1-Pad8)") (class "Default")
      (node (ref "P1") (pin "8") (pinfunction "8_8") (pintype "passive+no_connect"))
    )
  )
)
